# loud-esp-rev-f-schematic_easyeda.net
KiCad netlist of a schematic drawn in EasyEDA
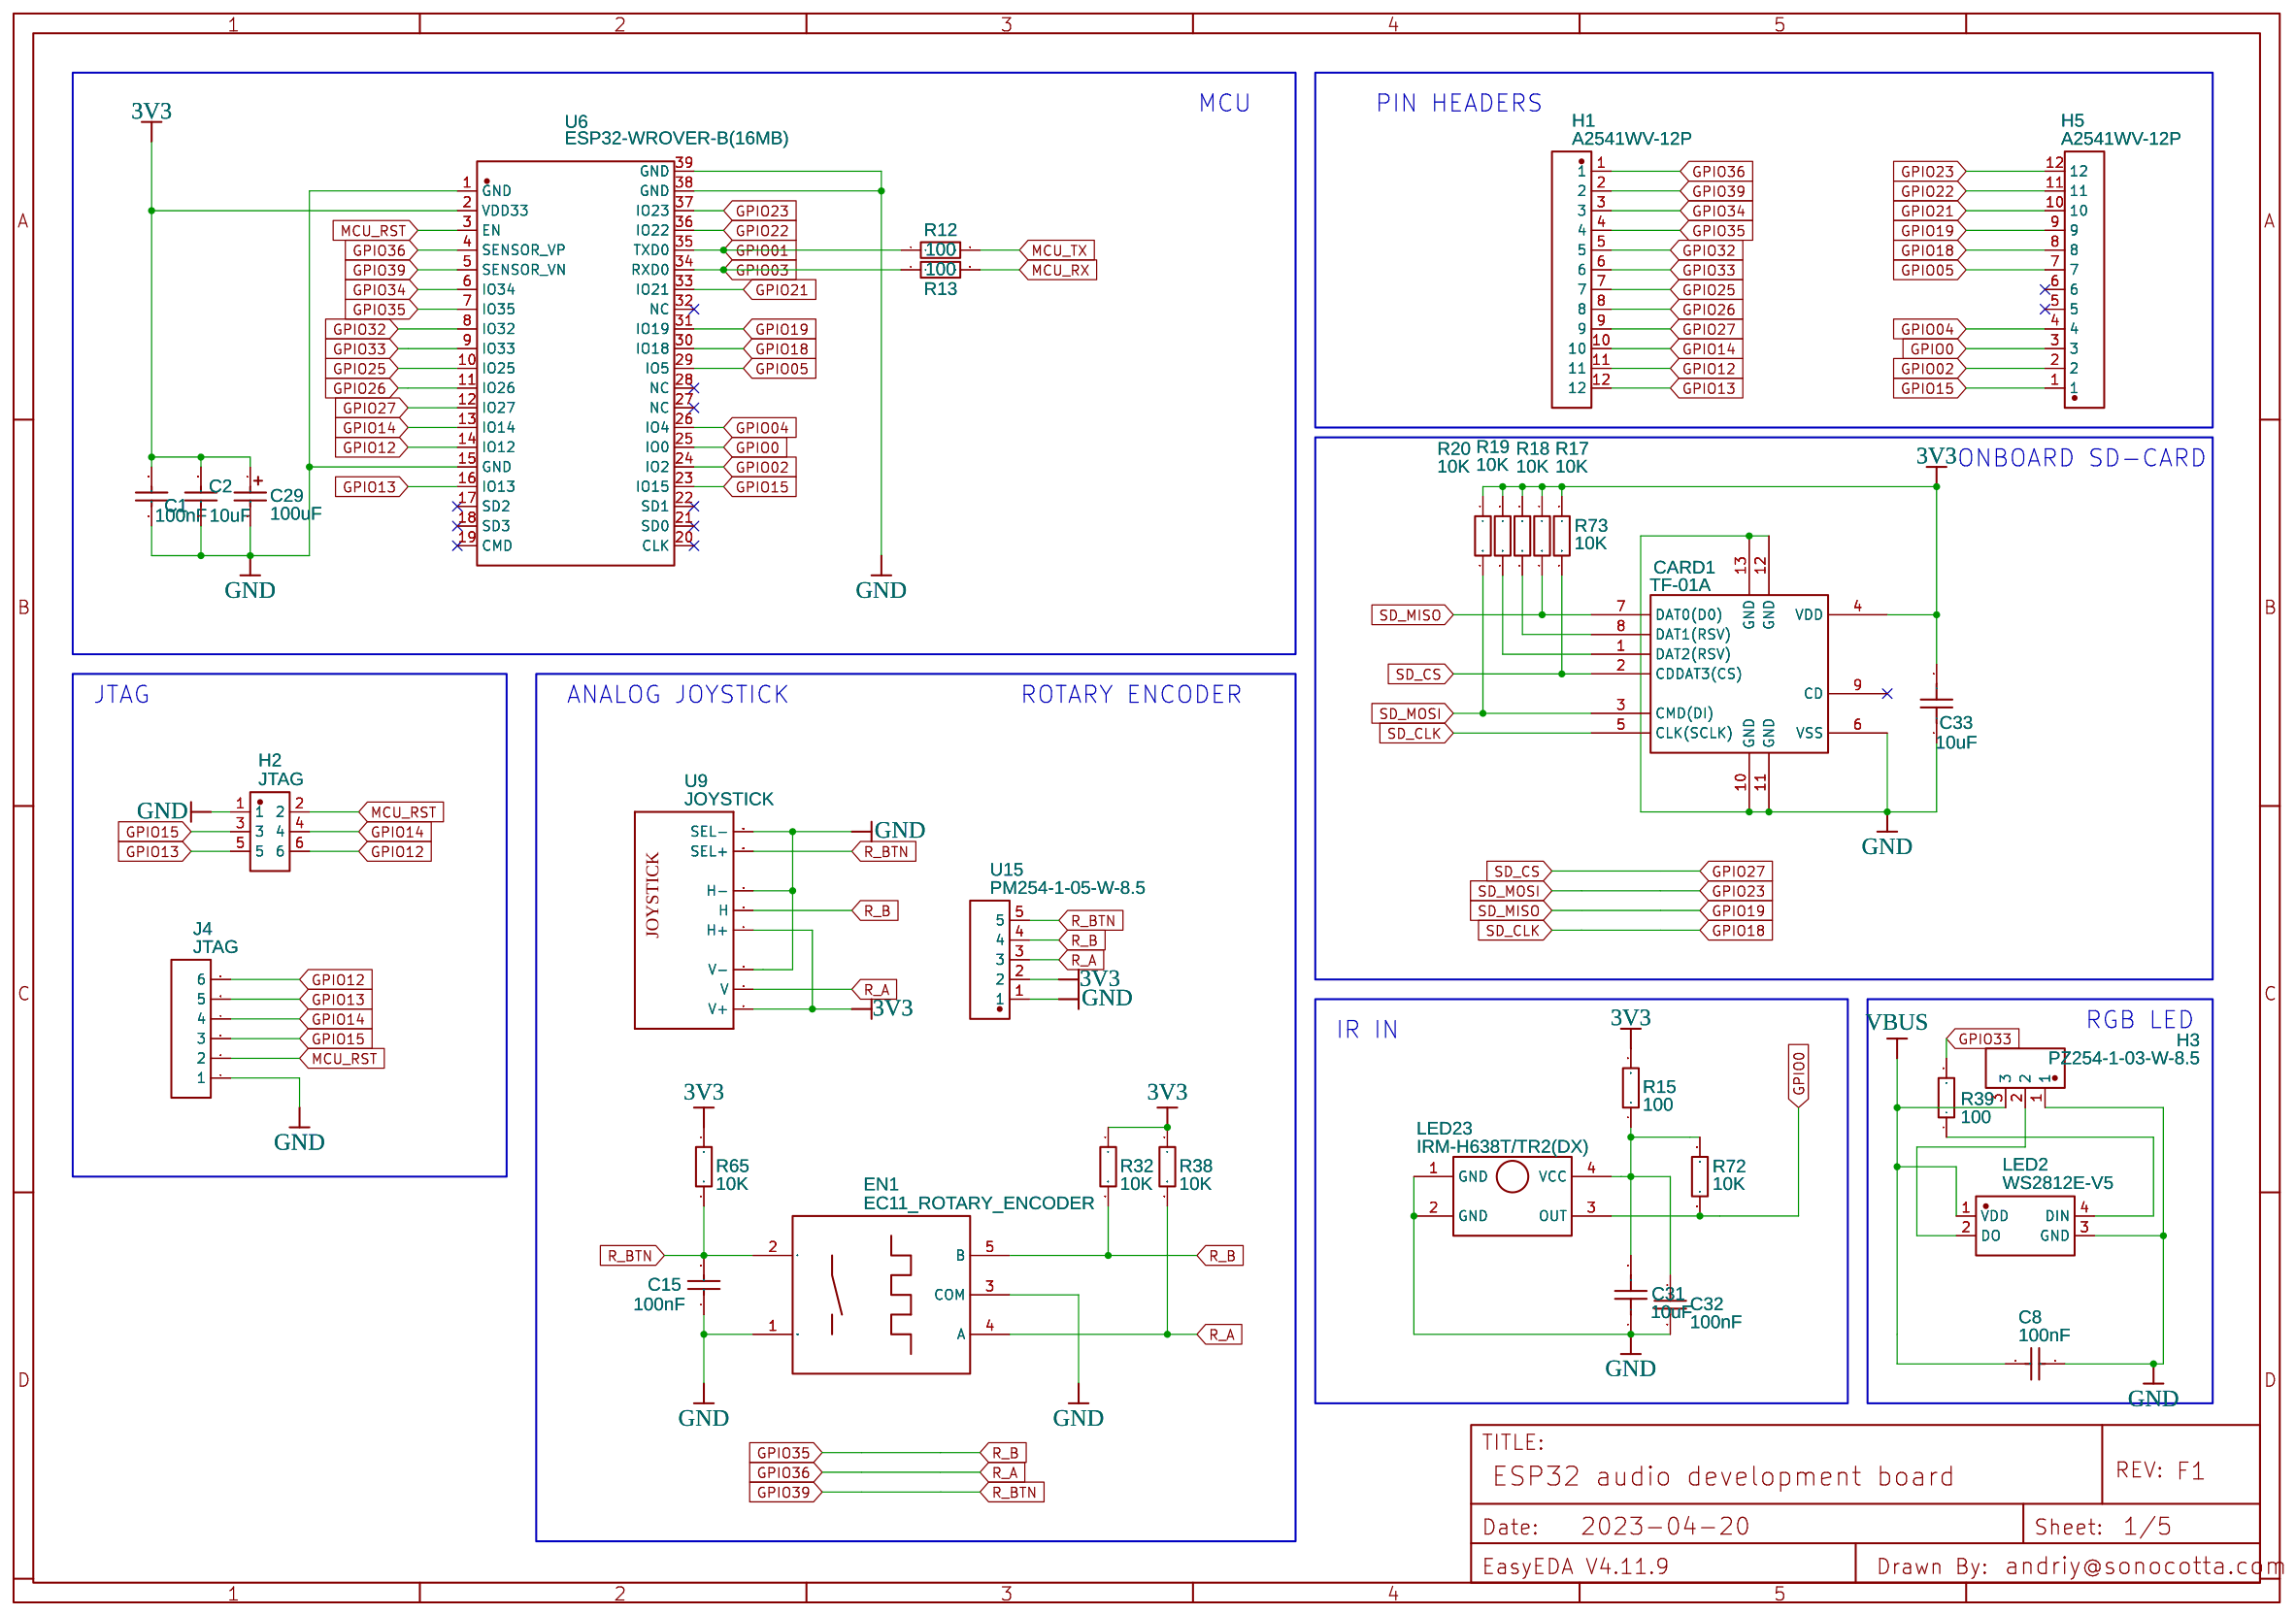
[diagram p0: MCU]
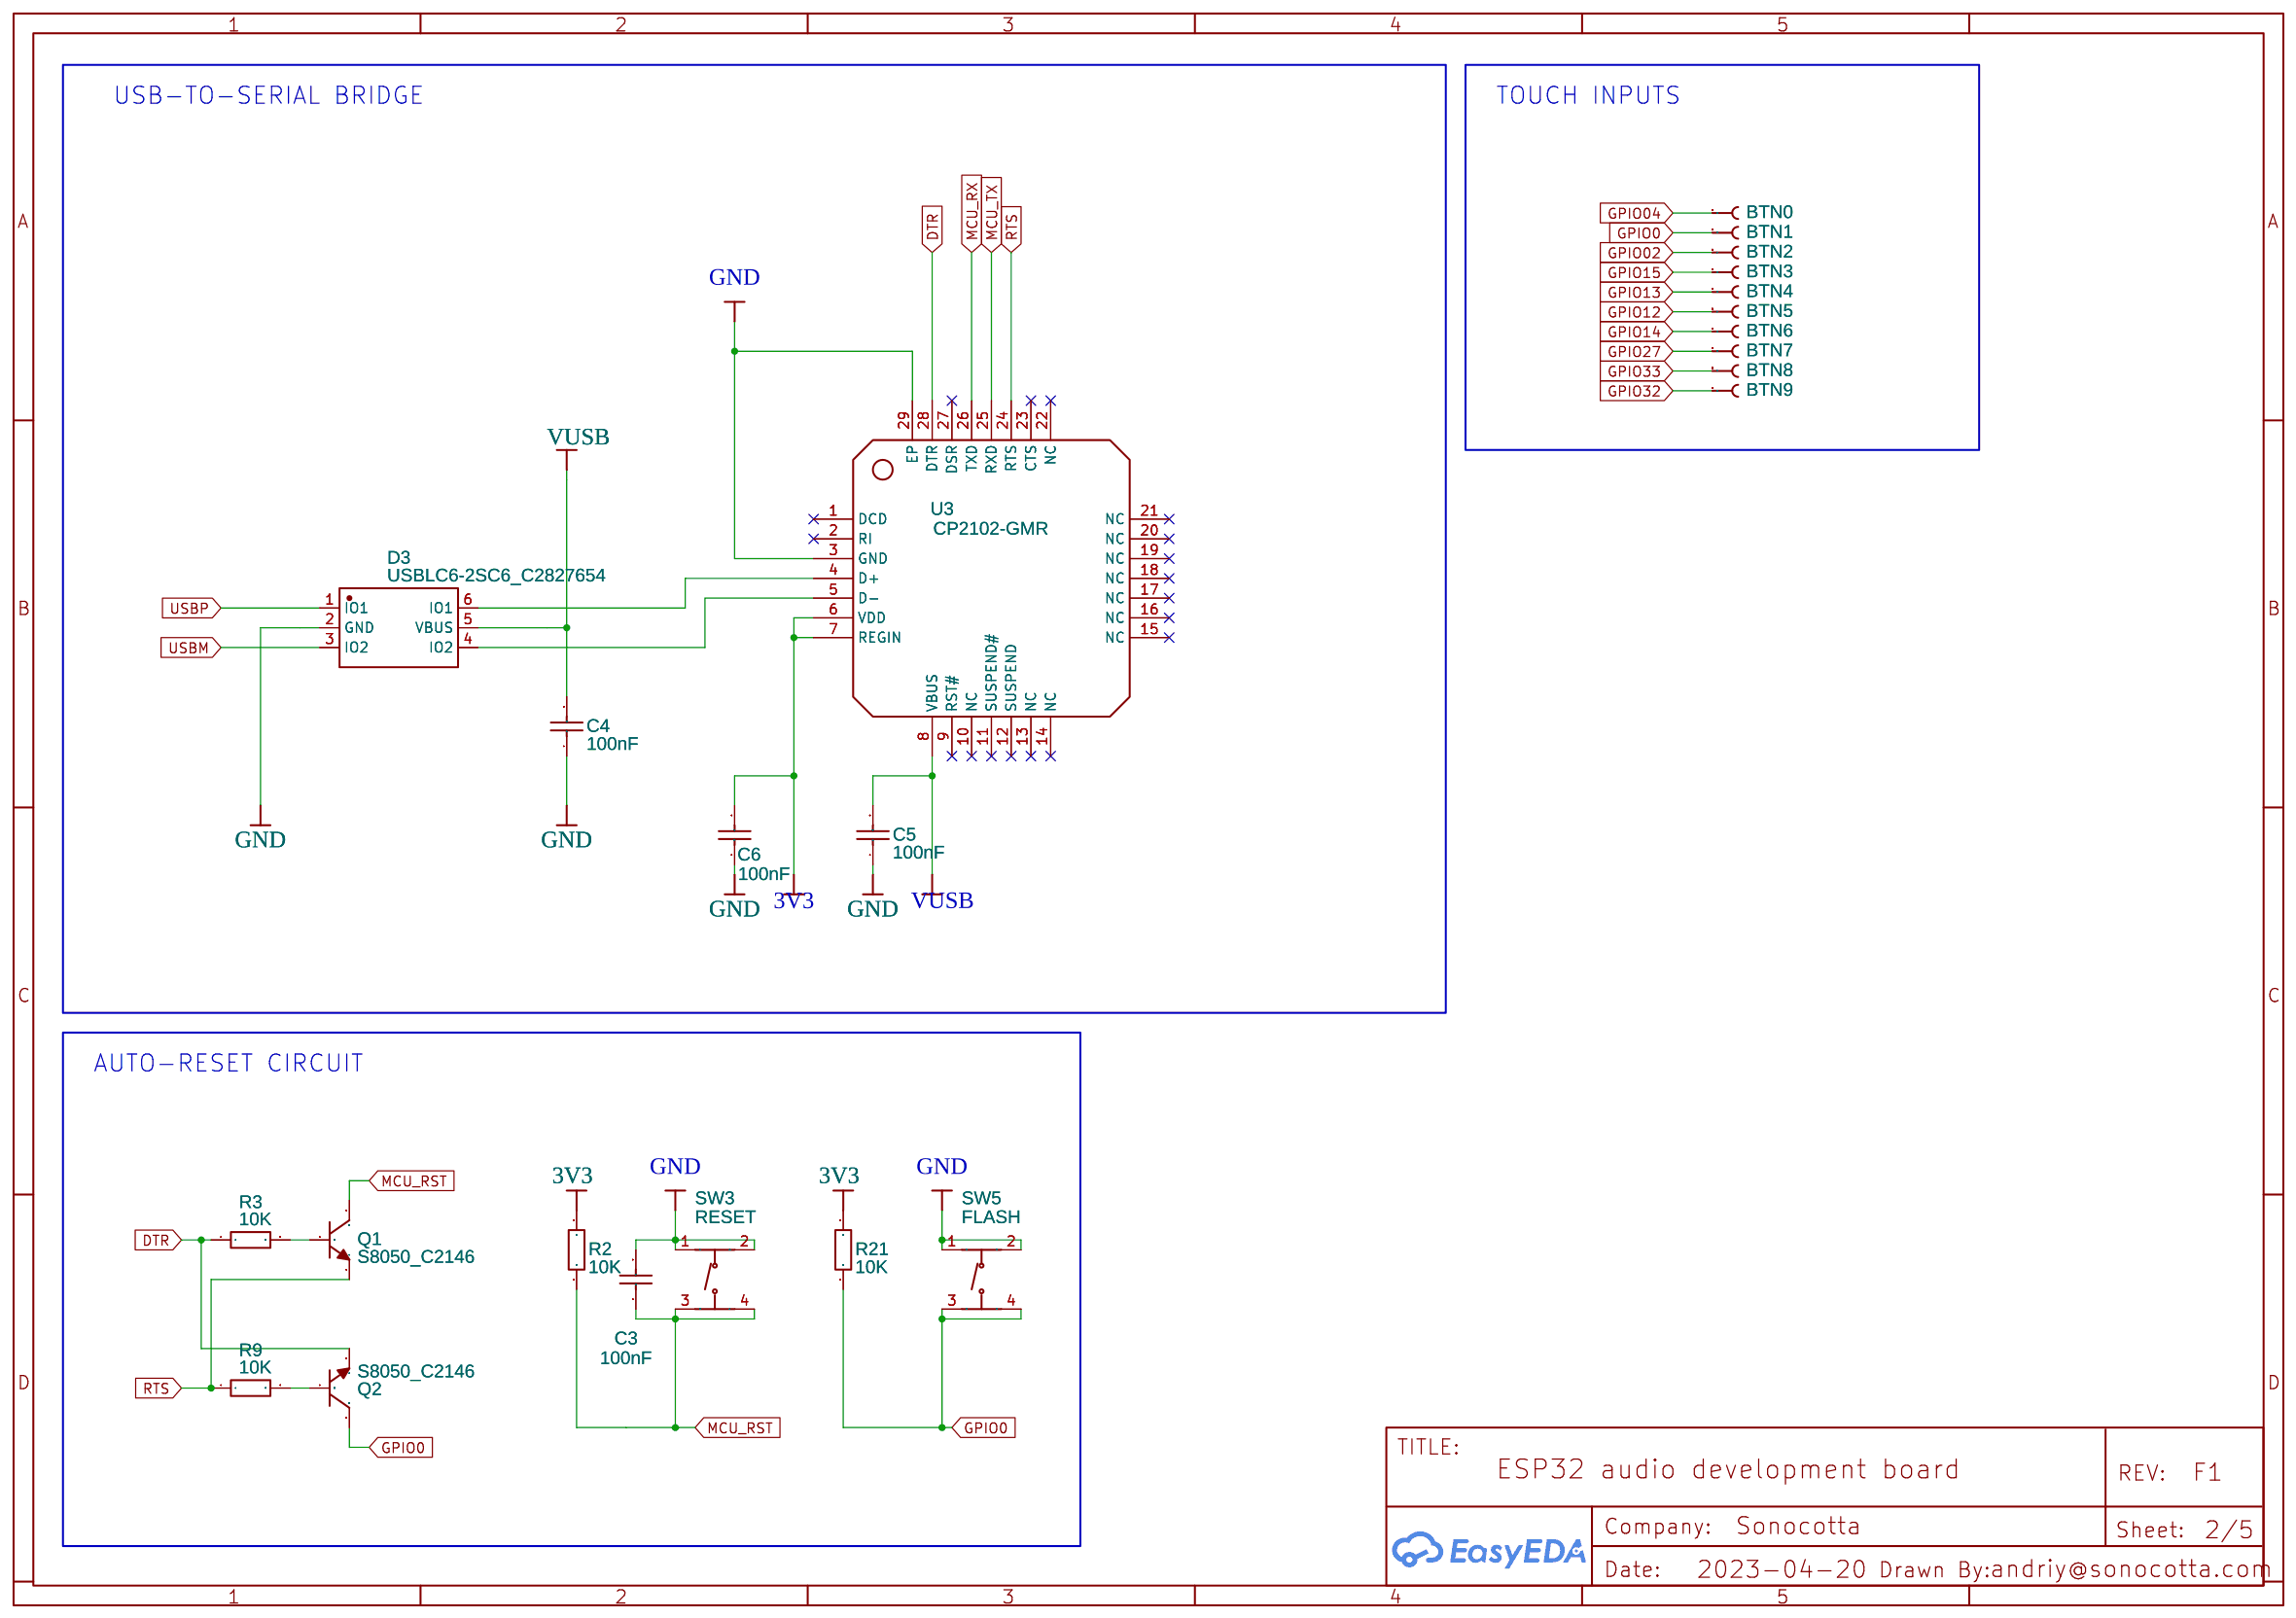
[diagram p1: SERIAL]
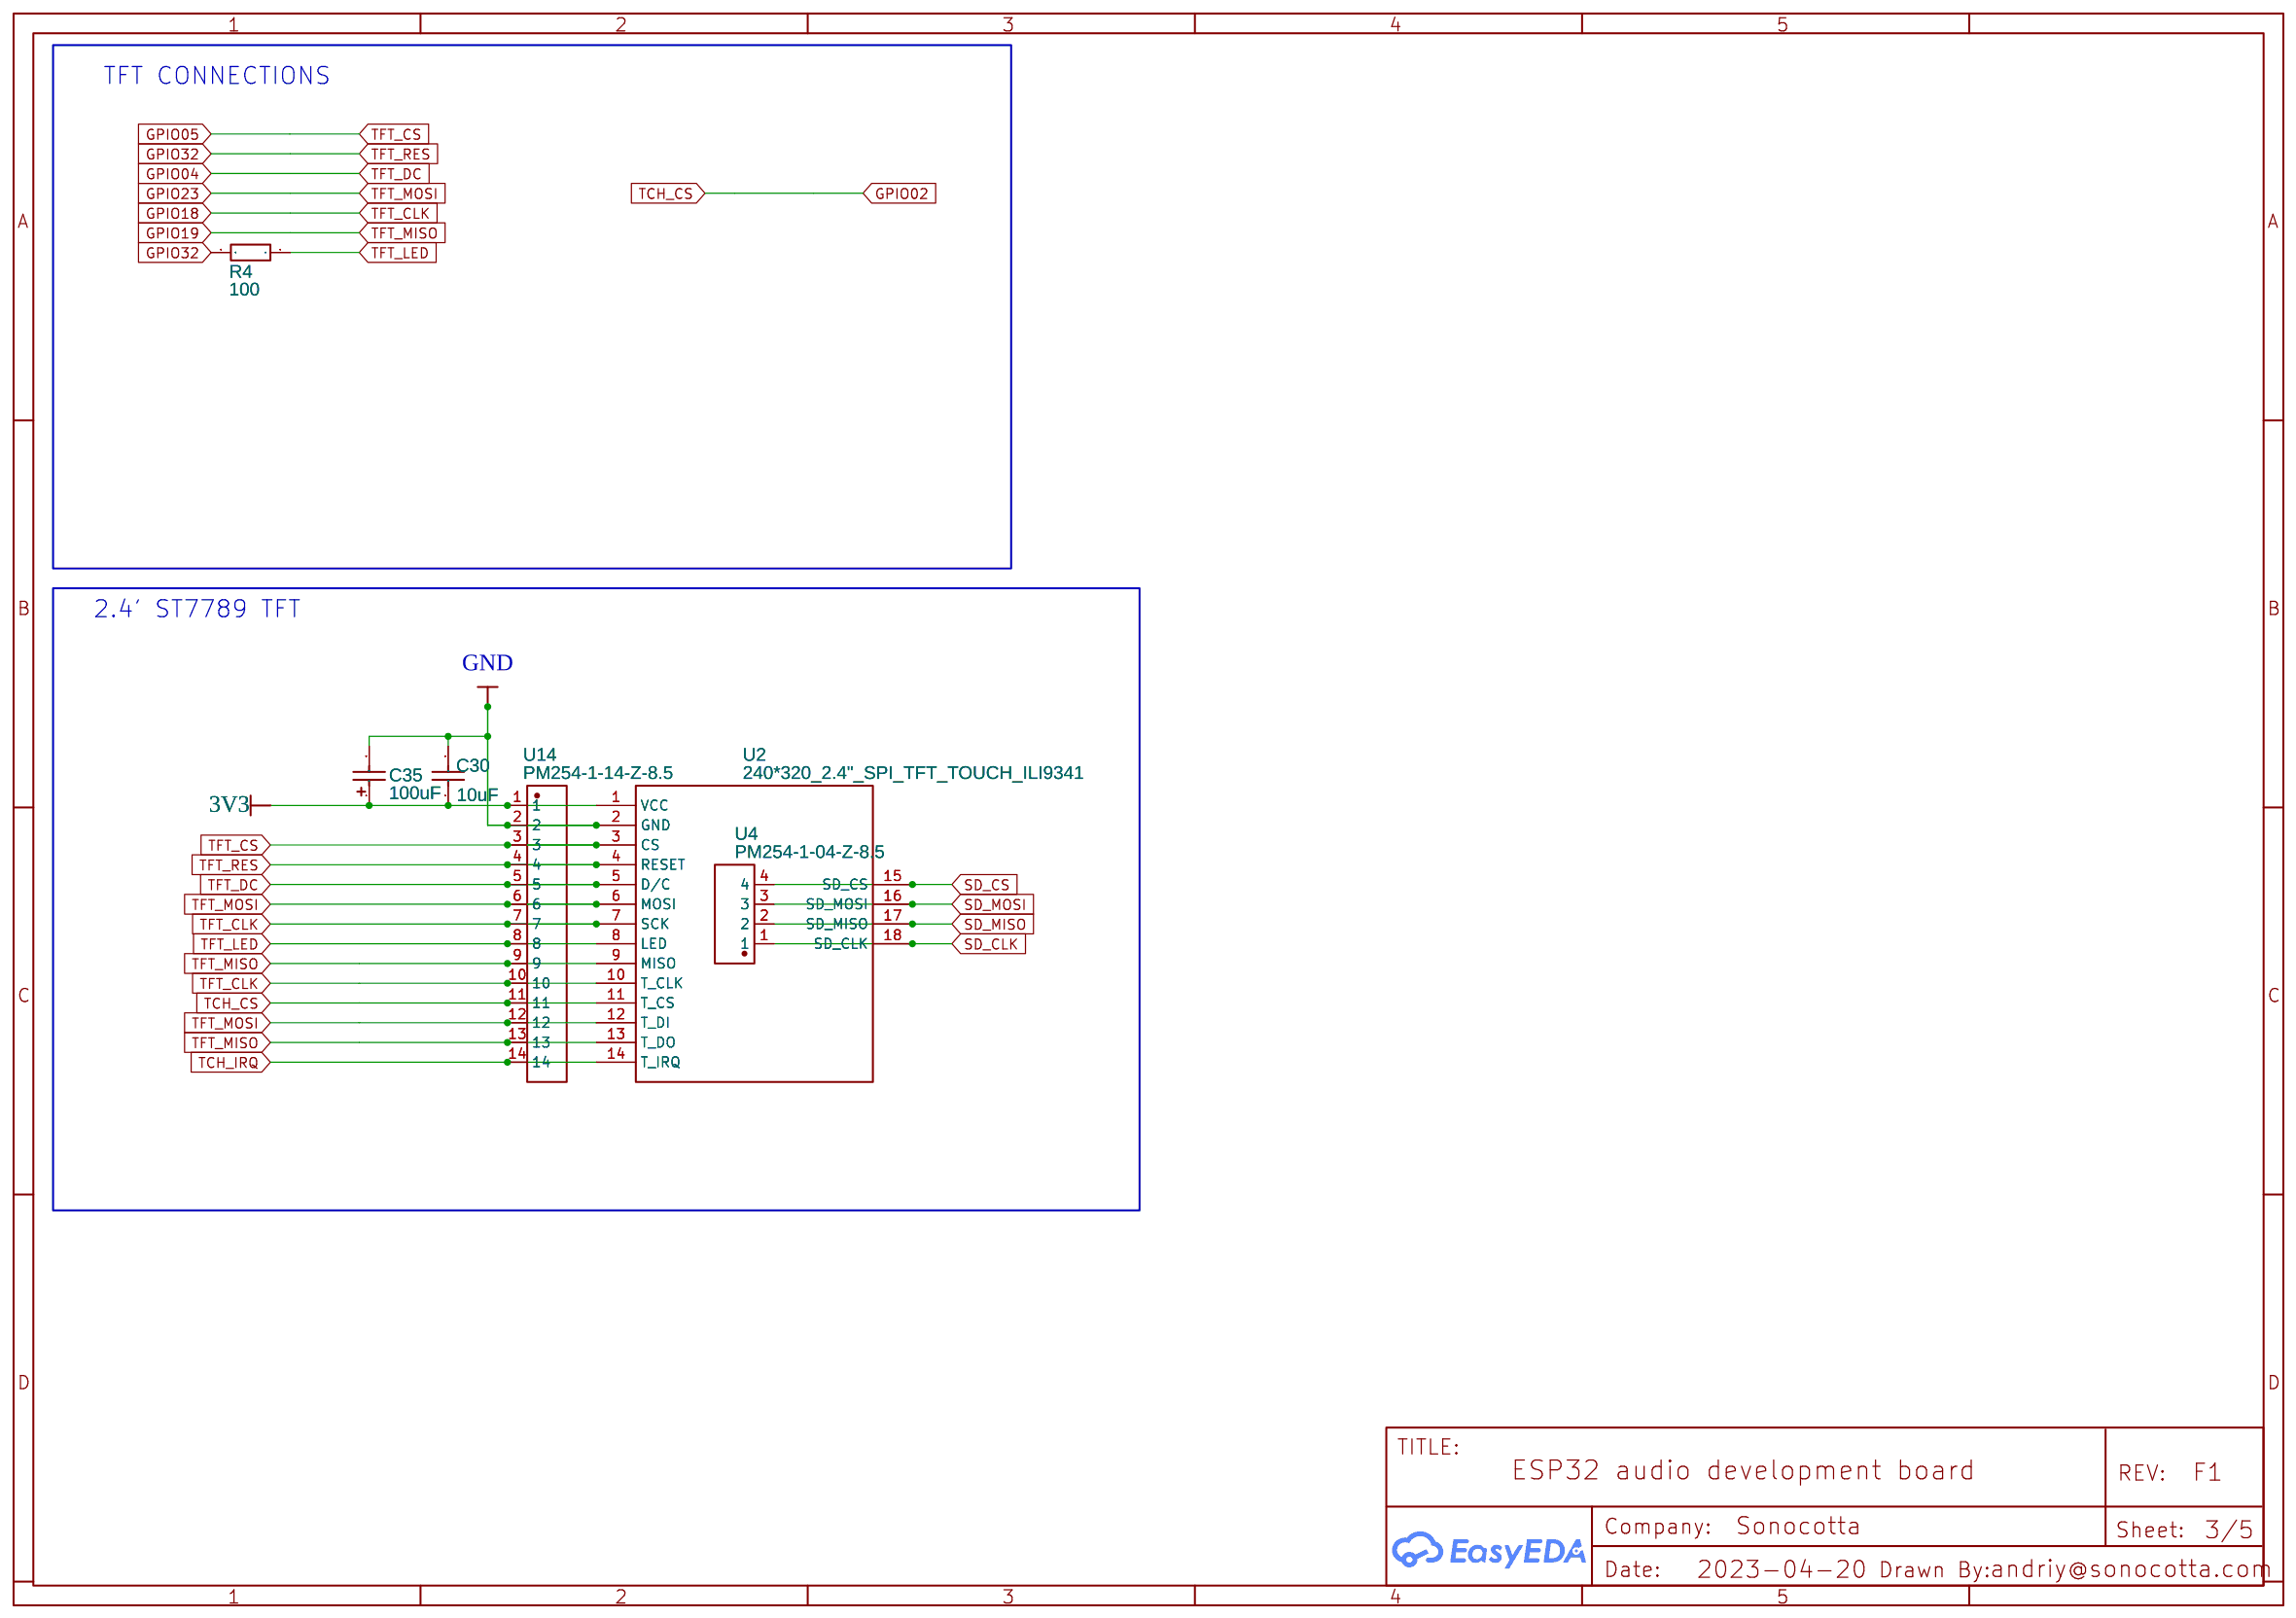
[diagram p2: VISUAL]
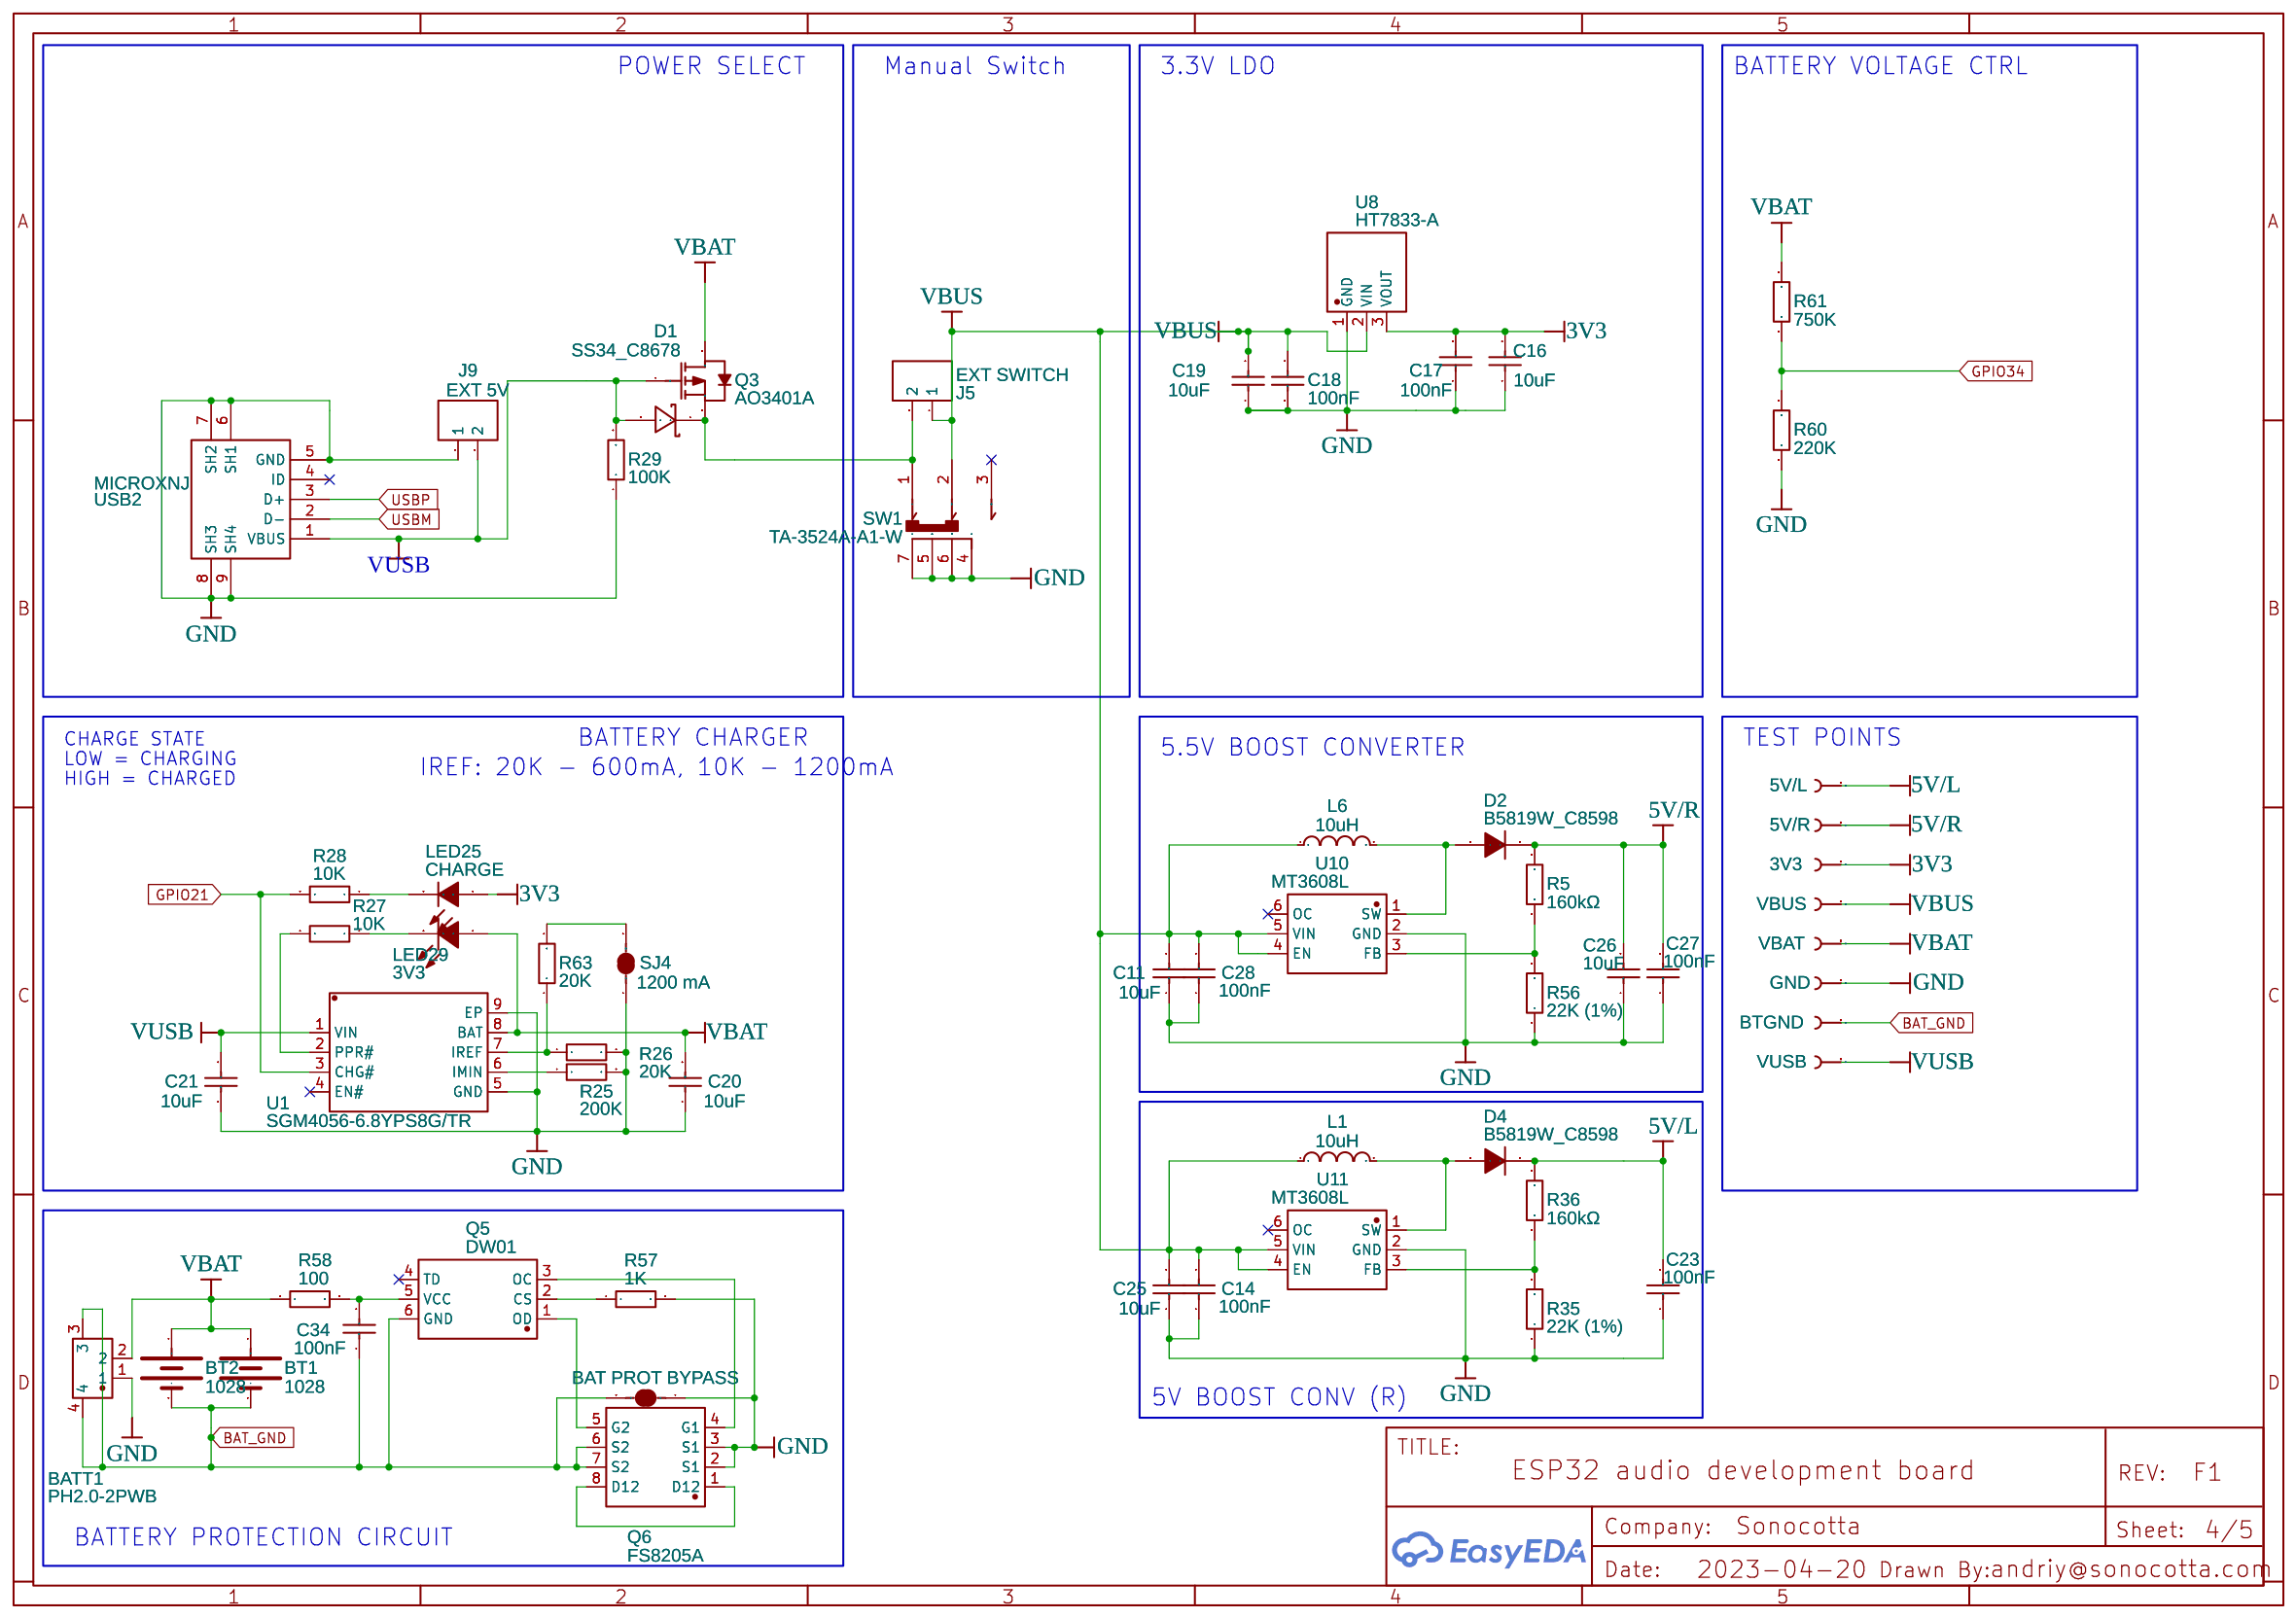
[diagram p3: POWER MGT]
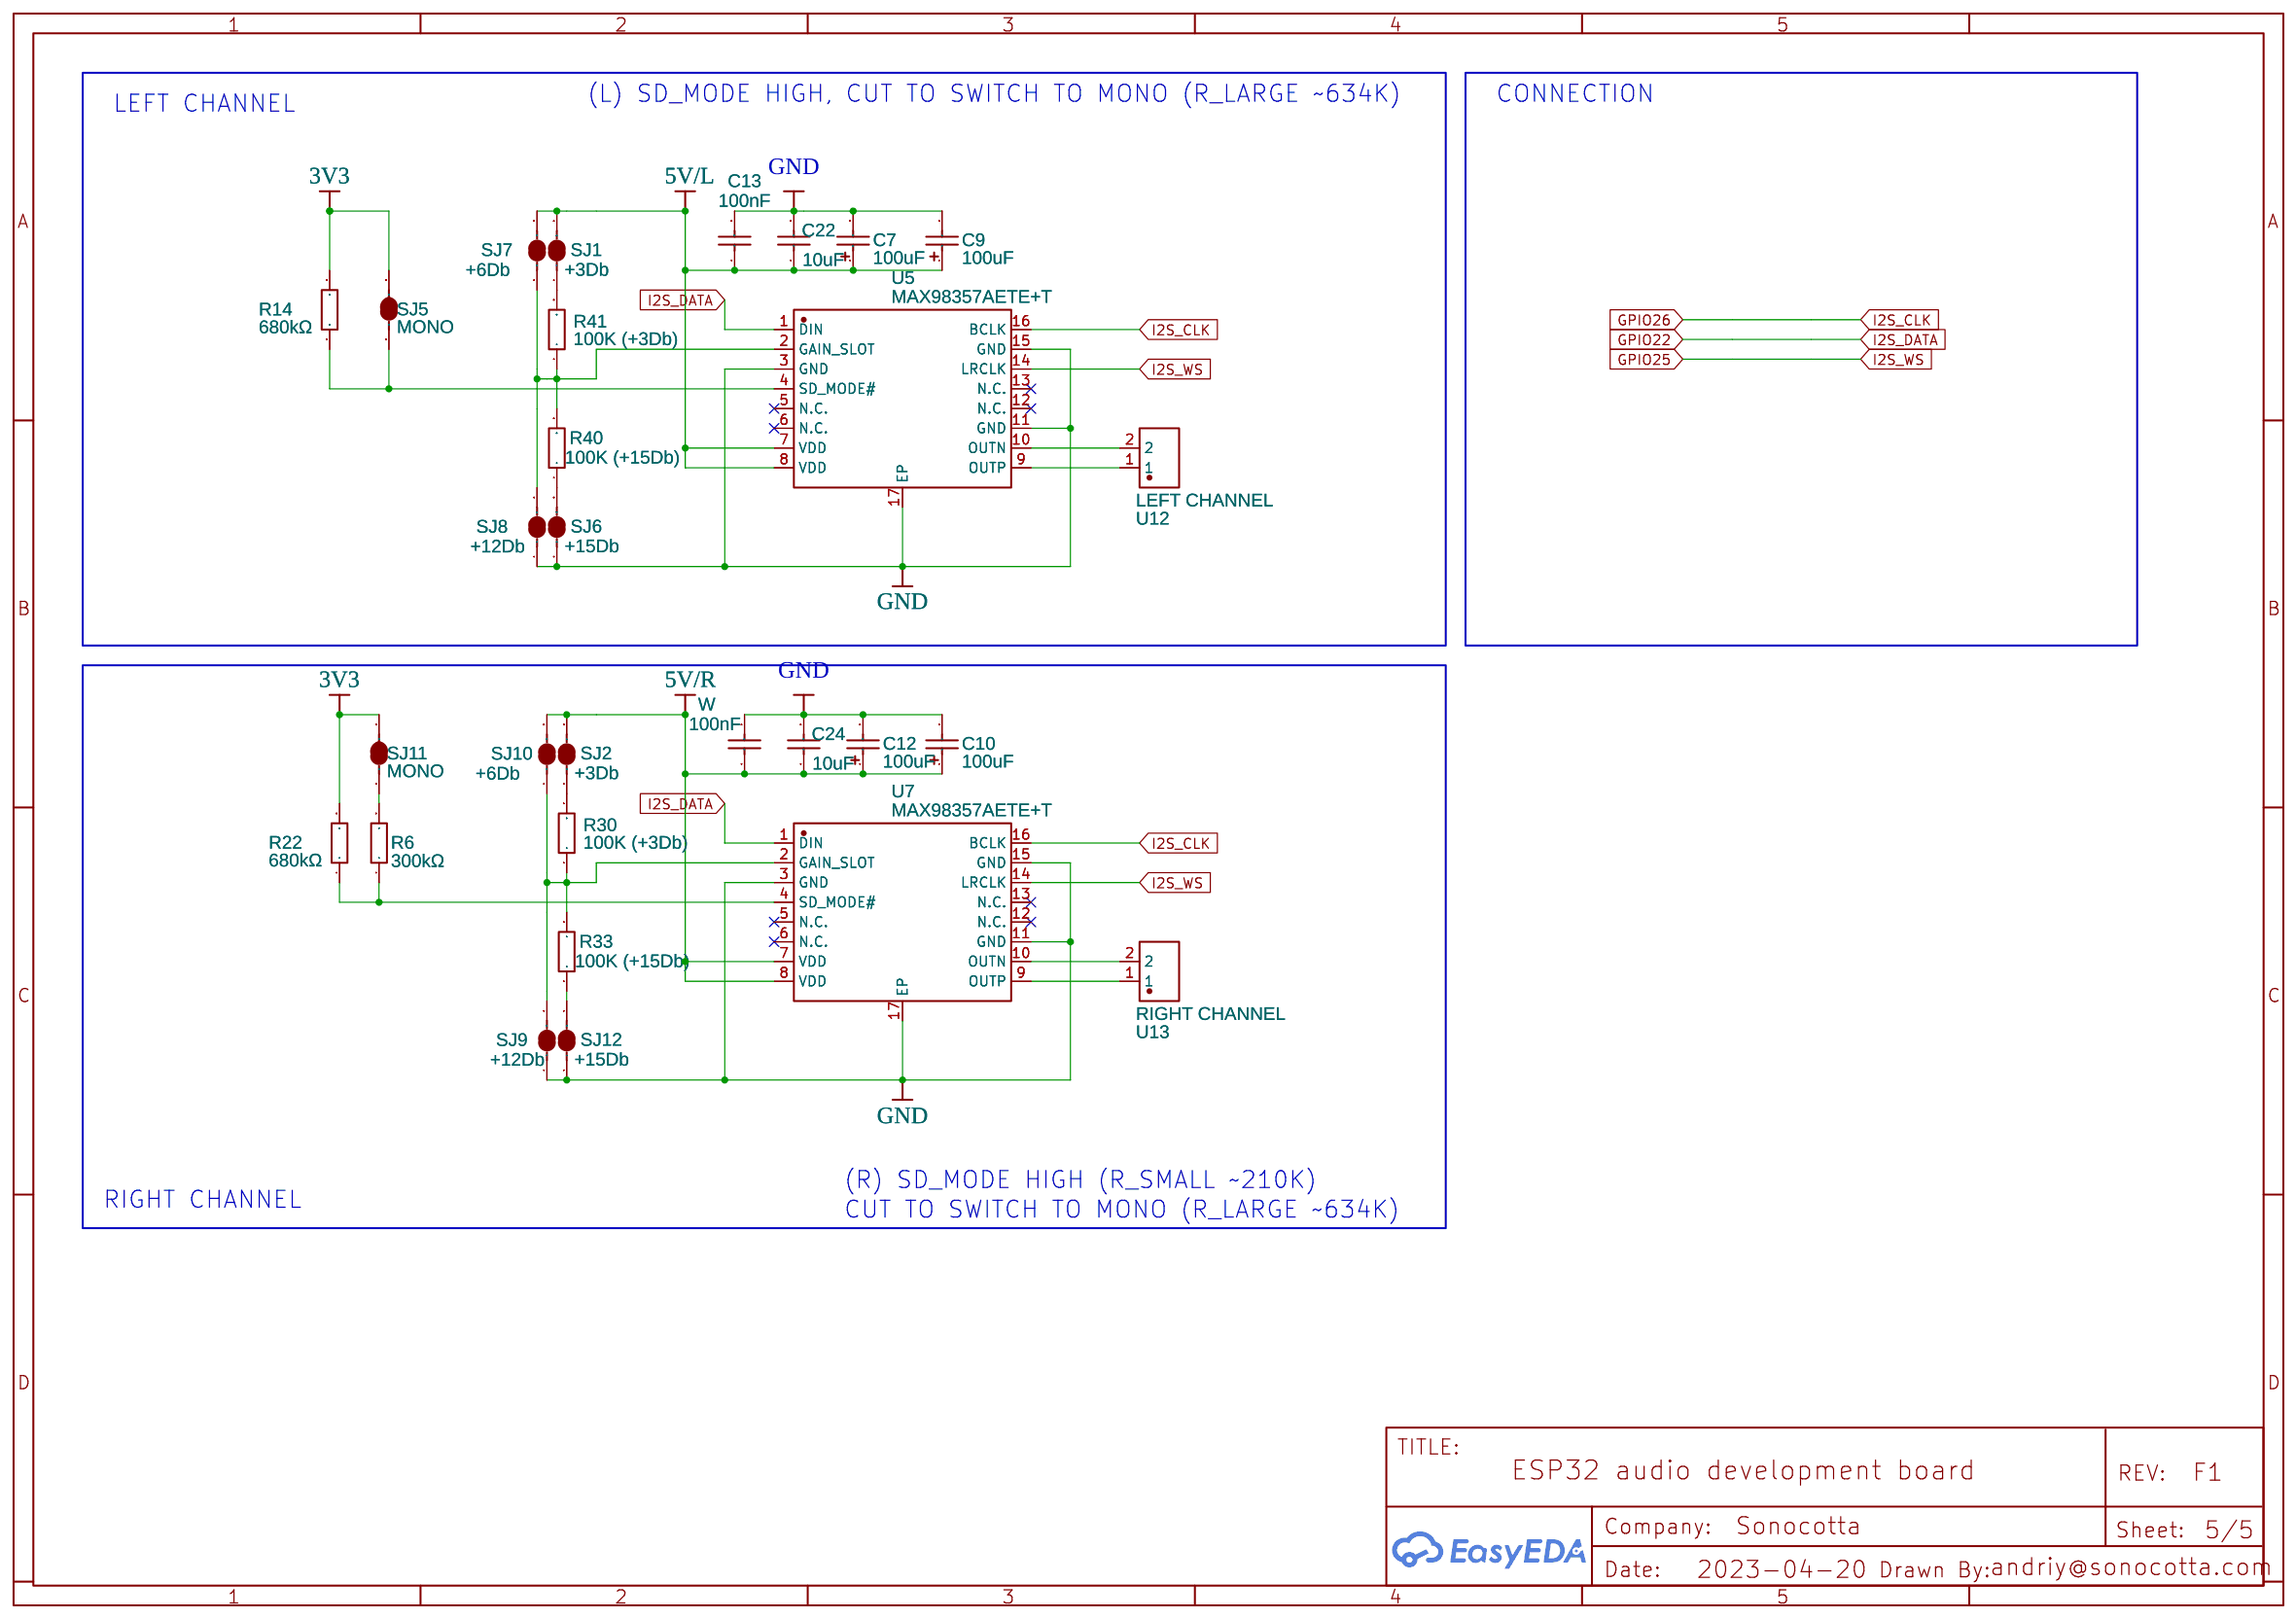
[diagram p4: DAC]

(export (version "E")
  (design (tool "Eeschema 10.0.6"))
  (components
    (comp (ref "C1")
      (value "100nF")
      (fields (field (name "Manufacturer Part") "CL05B104KO5NNNC") (field (name "Manufacturer") "SAMSUNG"))
      (libsource (lib "") (part "CL05B104KO5NNNC"))
    )
    (comp (ref "C2")
      (value "10uF")
      (fields (field (name "Manufacturer Part") "CL21A106KAYNNNE") (field (name "Manufacturer") "SAMSUNG"))
      (libsource (lib "") (part "CL21A106KAYNNNE"))
    )
    (comp (ref "C8")
      (value "100nF")
      (fields (field (name "Manufacturer Part") "CL05B104KO5NNNC") (field (name "Manufacturer") "SAMSUNG"))
      (libsource (lib "") (part "C0201X6S104K6R3NTA"))
    )
    (comp (ref "C15")
      (value "100nF")
      (fields (field (name "Manufacturer Part") "CL05B104KO5NNNC") (field (name "Manufacturer") "SAMSUNG"))
      (libsource (lib "") (part "CL05B104KO5NNNC"))
    )
    (comp (ref "C29")
      (value "100uF")
      (fields (field (name "Manufacturer Part") "TAJB107K006RNJ") (field (name "Manufacturer") "AVX"))
      (libsource (lib "") (part "TAJB107K006RNJ"))
    )
    (comp (ref "C31")
      (value "10uF")
      (fields (field (name "Manufacturer Part") "CL10A106KP8NNNC") (field (name "Manufacturer") "SAMSUNG"))
      (libsource (lib "") (part "JMK107ABJ106KA-T"))
    )
    (comp (ref "C32")
      (value "100nF")
      (fields (field (name "Manufacturer Part") "CL05B104KO5NNNC") (field (name "Manufacturer") "SAMSUNG"))
      (libsource (lib "") (part "CL05B104KO5NNNC_1"))
    )
    (comp (ref "C33")
      (value "10uF")
      (fields (field (name "Manufacturer Part") "CL10A106KP8NNNC") (field (name "Manufacturer") "SAMSUNG"))
      (libsource (lib "") (part "JMK107ABJ106KA-T"))
    )
    (comp (ref "CARD1")
      (value "TF-01A")
      (fields (field (name "Manufacturer") "HRO"))
      (libsource (lib "") (part "TF-01A"))
    )
    (comp (ref "EN1")
      (value "EC11_ROTARY_ENCODER")
      (fields (field (name "Manufacturer Part") "EC11 Rotary Encoder"))
      (libsource (lib "") (part "EC11_ROTARY_ENCODER"))
    )
    (comp (ref "H1")
      (value "A2541WV-12P")
      (fields (field (name "Manufacturer") "Changjiang Connectors"))
      (libsource (lib "") (part "A2541WV-12P_1"))
    )
    (comp (ref "H2")
      (value "JTAG")
      (fields
        (field (name "Manufacturer Part") "X4621WV-2×03I-C28D40")
        (field (name "Manufacturer") "XKB Connectivity")
      )
      (libsource (lib "") (part "X4621WV-2×03I-C28D40"))
    )
    (comp (ref "H3")
      (value "PZ254-1-03-W-8.5")
      (fields (field (name "Manufacturer") "HCTL(华灿天禄)"))
      (libsource (lib "") (part "PZ254-1-03-W-8.5"))
    )
    (comp (ref "H5")
      (value "A2541WV-12P")
      (fields (field (name "Manufacturer") "Changjiang Connectors"))
      (libsource (lib "") (part "A2541WV-12P"))
    )
    (comp (ref "J4") (value "JTAG") (libsource (lib "") (part "HDR-M-2.54_1x6")))
    (comp (ref "LED2")
      (value "WS2812E-V5")
      (fields (field (name "Manufacturer") "worldsemi"))
      (libsource (lib "") (part "WS2812E-V5"))
    )
    (comp (ref "LED23")
      (value "IRM-H638T/TR2(DX)")
      (fields (field (name "Manufacturer") "Everlight Elec"))
      (libsource (lib "") (part "IRM-H638T/TR2(DX)"))
    )
    (comp (ref "R12")
      (value "100")
      (fields (field (name "Manufacturer Part") "0402WGF1000TCE") (field (name "Manufacturer") "UniOhm"))
      (libsource (lib "") (part "0402WGF1000TCE_1"))
    )
    (comp (ref "R13")
      (value "100")
      (fields (field (name "Manufacturer Part") "0402WGF1000TCE") (field (name "Manufacturer") "UniOhm"))
      (libsource (lib "") (part "0402WGF1000TCE_1"))
    )
    (comp (ref "R15")
      (value "100")
      (fields (field (name "Manufacturer Part") "0402WGF1000TCE") (field (name "Manufacturer") "UniOhm"))
      (libsource (lib "") (part "0402WGF1000TCE"))
    )
    (comp (ref "R17")
      (value "10K")
      (fields (field (name "Manufacturer Part") "0402WGF1002TCE") (field (name "Manufacturer") "UniOhm"))
      (libsource (lib "") (part "0402WGF1002TCE"))
    )
    (comp (ref "R18")
      (value "10K")
      (fields (field (name "Manufacturer Part") "0402WGF1002TCE") (field (name "Manufacturer") "UniOhm"))
      (libsource (lib "") (part "0402WGF1002TCE"))
    )
    (comp (ref "R19")
      (value "10K")
      (fields (field (name "Manufacturer Part") "0402WGF1002TCE") (field (name "Manufacturer") "UniOhm"))
      (libsource (lib "") (part "0402WGF1002TCE"))
    )
    (comp (ref "R20")
      (value "10K")
      (fields (field (name "Manufacturer Part") "0402WGF1002TCE") (field (name "Manufacturer") "UniOhm"))
      (libsource (lib "") (part "0402WGF1002TCE"))
    )
    (comp (ref "R32")
      (value "10K")
      (fields (field (name "Manufacturer Part") "0402WGF1002TCE") (field (name "Manufacturer") "UniOhm"))
      (libsource (lib "") (part "0402WGF1002TCE"))
    )
    (comp (ref "R38")
      (value "10K")
      (fields (field (name "Manufacturer Part") "0402WGF1002TCE") (field (name "Manufacturer") "UniOhm"))
      (libsource (lib "") (part "0402WGF1002TCE"))
    )
    (comp (ref "R39")
      (value "100")
      (fields (field (name "Manufacturer Part") "0402WGF1000TCE") (field (name "Manufacturer") "UniOhm"))
      (libsource (lib "") (part "0402WGF1000TCE"))
    )
    (comp (ref "R65")
      (value "10K")
      (fields (field (name "Manufacturer Part") "0402WGF1002TCE") (field (name "Manufacturer") "UniOhm"))
      (libsource (lib "") (part "0402WGF1002TCE"))
    )
    (comp (ref "R72")
      (value "10K")
      (fields (field (name "Manufacturer Part") "0402WGF1002TCE") (field (name "Manufacturer") "UniOhm"))
      (libsource (lib "") (part "0402WGF1002TCE"))
    )
    (comp (ref "R73")
      (value "10K")
      (fields (field (name "Manufacturer Part") "0402WGF1002TCE") (field (name "Manufacturer") "UniOhm"))
      (libsource (lib "") (part "0402WGF1002TCE"))
    )
    (comp (ref "U6")
      (value "ESP32-WROVER-B(16MB)")
      (fields (field (name "Manufacturer") "Espressif Systems"))
      (libsource (lib "") (part "ESP32-WROVER-B(16MB)"))
    )
    (comp (ref "U9") (value "JOYSTICK") (libsource (lib "") (part "JOYSTICK")))
    (comp (ref "U15")
      (value "PM254-1-05-W-8.5")
      (fields (field (name "Manufacturer") "HCTL(华灿天禄)"))
      (libsource (lib "") (part "PM254-1-05-W-8.5"))
    )
    (comp (ref "BTN0") (value "SENSOR CAP 1") (libsource (lib "") (part "TEST-POINT2")))
    (comp (ref "BTN1") (value "SENSOR CAP 1") (libsource (lib "") (part "TEST-POINT2")))
    (comp (ref "BTN2") (value "SENSOR CAP 1") (libsource (lib "") (part "TEST-POINT2")))
    (comp (ref "BTN3") (value "SENSOR CAP 1") (libsource (lib "") (part "TEST-POINT2")))
    (comp (ref "BTN4") (value "SENSOR CAP 1") (libsource (lib "") (part "TEST-POINT2")))
    (comp (ref "BTN5") (value "SENSOR CAP 1") (libsource (lib "") (part "TEST-POINT2")))
    (comp (ref "BTN6") (value "SENSOR CAP 1") (libsource (lib "") (part "TEST-POINT2")))
    (comp (ref "BTN7") (value "SENSOR CAP 1") (libsource (lib "") (part "TEST-POINT2")))
    (comp (ref "BTN8") (value "SENSOR CAP 1") (libsource (lib "") (part "TEST-POINT2")))
    (comp (ref "BTN9") (value "SENSOR CAP 1") (libsource (lib "") (part "TEST-POINT2")))
    (comp (ref "C3")
      (value "100nF")
      (fields
        (field (name "BOM_Manufacturer Part") "CL05B104KO5NNNC")
        (field (name "BOM_Supplier Part") "C1525")
      )
      (libsource (lib "") (part "CL05B104KO5NNNC"))
    )
    (comp (ref "C4")
      (value "100nF")
      (fields
        (field (name "BOM_Manufacturer Part") "CL05B104KO5NNNC")
        (field (name "BOM_Supplier Part") "C1525")
      )
      (libsource (lib "") (part "CL05B104KO5NNNC"))
    )
    (comp (ref "C5")
      (value "100nF")
      (fields
        (field (name "BOM_Manufacturer Part") "CL05B104KO5NNNC")
        (field (name "BOM_Supplier Part") "C1525")
      )
      (libsource (lib "") (part "CL05B104KO5NNNC"))
    )
    (comp (ref "C6")
      (value "100nF")
      (fields
        (field (name "BOM_Manufacturer Part") "CL05B104KO5NNNC")
        (field (name "BOM_Supplier Part") "C1525")
      )
      (libsource (lib "") (part "CL05B104KO5NNNC"))
    )
    (comp (ref "D3")
      (value "USBLC6-2SC6_C2827654")
      (fields
        (field (name "BOM_Manufacturer Part") "USBLC6-2SC6")
        (field (name "BOM_Supplier Part") "C2827654")
      )
      (libsource (lib "") (part "USBLC6-2SC6_C2827654"))
    )
    (comp (ref "Q1")
      (value "S8050_C2146")
      (fields (field (name "BOM_Manufacturer Part") "S8050") (field (name "BOM_Supplier Part") "C2146"))
      (libsource (lib "") (part "S8050_C2146"))
    )
    (comp (ref "Q2")
      (value "S8050_C2146")
      (fields (field (name "BOM_Manufacturer Part") "S8050") (field (name "BOM_Supplier Part") "C2146"))
      (libsource (lib "") (part "S8050_C2146_1"))
    )
    (comp (ref "R2")
      (value "10K")
      (fields
        (field (name "BOM_Manufacturer Part") "0402WGF1002TCE")
        (field (name "BOM_Supplier Part") "C25744")
      )
      (libsource (lib "") (part "0402WGF1002TCE_1"))
    )
    (comp (ref "R3")
      (value "10K")
      (fields
        (field (name "BOM_Manufacturer Part") "0402WGF1002TCE")
        (field (name "BOM_Supplier Part") "C25744")
      )
      (libsource (lib "") (part "0402WGF1002TCE"))
    )
    (comp (ref "R9")
      (value "10K")
      (fields
        (field (name "BOM_Manufacturer Part") "0402WGF1002TCE")
        (field (name "BOM_Supplier Part") "C25744")
      )
      (libsource (lib "") (part "0402WGF1002TCE"))
    )
    (comp (ref "R21")
      (value "10K")
      (fields
        (field (name "BOM_Manufacturer Part") "0402WGF1002TCE")
        (field (name "BOM_Supplier Part") "C25744")
      )
      (libsource (lib "") (part "0402WGF1002TCE_1"))
    )
    (comp (ref "SW3")
      (value "RESET")
      (fields
        (field (name "BOM_Manufacturer Part") "TS-1187A-B-A-B")
        (field (name "BOM_Supplier Part") "C318884")
      )
      (libsource (lib "") (part "TS-1187A-B-A-B"))
    )
    (comp (ref "SW5")
      (value "FLASH")
      (fields
        (field (name "BOM_Manufacturer Part") "TS-1187A-B-A-B")
        (field (name "BOM_Supplier Part") "C318884")
      )
      (libsource (lib "") (part "TS-1187A-B-A-B"))
    )
    (comp (ref "U3")
      (value "CP2102-GMR")
      (fields (field (name "BOM_Supplier Part") "C6568"))
      (libsource (lib "") (part "CP2102-GMR"))
    )
    (comp (ref "C30")
      (value "10uF")
      (fields
        (field (name "BOM_Manufacturer Part") "CL21A106KAYNNNE")
        (field (name "BOM_Supplier Part") "C15850")
      )
      (libsource (lib "") (part "CL21A106KAYNNNE"))
    )
    (comp (ref "C35")
      (value "100uF")
      (fields
        (field (name "BOM_Manufacturer Part") "TAJB107K006RNJ")
        (field (name "BOM_Supplier Part") "C16133")
      )
      (libsource (lib "") (part "TAJB107K006RNJ"))
    )
    (comp (ref "R4")
      (value "100")
      (fields
        (field (name "BOM_Manufacturer Part") "0402WGF1000TCE")
        (field (name "BOM_Supplier Part") "C25076")
      )
      (libsource (lib "") (part "0402WGF1000TCE"))
    )
    (comp (ref "U2")
      (value "240*320_2.4\"_SPI_TFT_TOUCH_ILI9341")
      (libsource (lib "") (part "240*320_2.4{dblquote}_SPI_TFT_TOUCH_ILI9341"))
    )
    (comp (ref "U4")
      (value "PM254-1-04-Z-8.5")
      (fields (field (name "BOM_Supplier Part") "C2897367"))
      (libsource (lib "") (part "PM254-1-04-Z-8.5"))
    )
    (comp (ref "U14")
      (value "PM254-1-14-Z-8.5")
      (fields (field (name "BOM_Supplier Part") "C2897377"))
      (libsource (lib "") (part "PM254-1-14-Z-8.5"))
    )
    (comp (ref "3V3") (value "SENSOR CAP 1") (libsource (lib "") (part "TEST-POINT2_2")))
    (comp (ref "5V/L") (value "SENSOR CAP 1") (libsource (lib "") (part "TEST-POINT2_1")))
    (comp (ref "5V/R") (value "SENSOR CAP 1") (libsource (lib "") (part "TEST-POINT2_3")))
    (comp (ref "BATT1")
      (value "PH2.0-2PWB")
      (fields
        (field (name "BOM_Manufacturer Part") "PH2.0-2PWB Horizontal")
        (field (name "BOM_Supplier Part") "C47647")
      )
      (libsource (lib "") (part "PH2.0-2PWB"))
    )
    (comp (ref "BT1")
      (value "1028")
      (fields (field (name "BOM_Supplier Part") "C238063"))
      (libsource (lib "") (part "1028"))
    )
    (comp (ref "BT2")
      (value "1028")
      (fields (field (name "BOM_Supplier Part") "C238063"))
      (libsource (lib "") (part "1028"))
    )
    (comp (ref "BTGND") (value "SENSOR CAP 1") (libsource (lib "") (part "TEST-POINT2_7")))
    (comp (ref "C11")
      (value "10uF")
      (fields
        (field (name "BOM_Manufacturer Part") "CL21A106KAYNNNE")
        (field (name "BOM_Supplier Part") "C15850")
      )
      (libsource (lib "") (part "CL21A106KAYNNNE"))
    )
    (comp (ref "C14")
      (value "100nF")
      (fields
        (field (name "BOM_Manufacturer Part") "CL05B104KO5NNNC")
        (field (name "BOM_Supplier Part") "C1525")
      )
      (libsource (lib "") (part "CL05B104KO5NNNC"))
    )
    (comp (ref "C16")
      (value "10uF")
      (fields
        (field (name "BOM_Manufacturer Part") "CL21A106KAYNNNE")
        (field (name "BOM_Supplier Part") "C15850")
      )
      (libsource (lib "") (part "CL21A106KAYNNNE"))
    )
    (comp (ref "C17")
      (value "100nF")
      (fields
        (field (name "BOM_Manufacturer Part") "CL05B104KO5NNNC")
        (field (name "BOM_Supplier Part") "C1525")
      )
      (libsource (lib "") (part "CL05B104KO5NNNC"))
    )
    (comp (ref "C18")
      (value "100nF")
      (fields
        (field (name "BOM_Manufacturer Part") "CL05B104KO5NNNC")
        (field (name "BOM_Supplier Part") "C1525")
      )
      (libsource (lib "") (part "CL05B104KO5NNNC"))
    )
    (comp (ref "C19")
      (value "10uF")
      (fields
        (field (name "BOM_Manufacturer Part") "CL21A106KAYNNNE")
        (field (name "BOM_Supplier Part") "C15850")
      )
      (libsource (lib "") (part "CL21A106KAYNNNE"))
    )
    (comp (ref "C20")
      (value "10uF")
      (fields
        (field (name "BOM_Manufacturer Part") "CL21A106KAYNNNE")
        (field (name "BOM_Supplier Part") "C15850")
      )
      (libsource (lib "") (part "CL21A106KAYNNNE"))
    )
    (comp (ref "C21")
      (value "10uF")
      (fields
        (field (name "BOM_Manufacturer Part") "CL21A106KAYNNNE")
        (field (name "BOM_Supplier Part") "C15850")
      )
      (libsource (lib "") (part "CL21A106KAYNNNE"))
    )
    (comp (ref "C23")
      (value "100nF")
      (fields
        (field (name "BOM_Manufacturer Part") "CL05B104KO5NNNC")
        (field (name "BOM_Supplier Part") "C1525")
      )
      (libsource (lib "") (part "CL05B104KO5NNNC"))
    )
    (comp (ref "C25")
      (value "10uF")
      (fields
        (field (name "BOM_Manufacturer Part") "CL21A106KAYNNNE")
        (field (name "BOM_Supplier Part") "C15850")
      )
      (libsource (lib "") (part "CL21A106KAYNNNE"))
    )
    (comp (ref "C26")
      (value "10uF")
      (fields
        (field (name "BOM_Manufacturer Part") "CL21A106KAYNNNE")
        (field (name "BOM_Supplier Part") "C15850")
      )
      (libsource (lib "") (part "CL21A106KAYNNNE"))
    )
    (comp (ref "C27")
      (value "100nF")
      (fields
        (field (name "BOM_Manufacturer Part") "CL05B104KO5NNNC")
        (field (name "BOM_Supplier Part") "C1525")
      )
      (libsource (lib "") (part "CL05B104KO5NNNC"))
    )
    (comp (ref "C28")
      (value "100nF")
      (fields
        (field (name "BOM_Manufacturer Part") "CL05B104KO5NNNC")
        (field (name "BOM_Supplier Part") "C1525")
      )
      (libsource (lib "") (part "CL05B104KO5NNNC"))
    )
    (comp (ref "C34")
      (value "100nF")
      (fields
        (field (name "BOM_Manufacturer Part") "CL05B104KO5NNNC")
        (field (name "BOM_Supplier Part") "C1525")
      )
      (libsource (lib "") (part "CL05B104KO5NNNC"))
    )
    (comp (ref "D1")
      (value "SS34_C8678")
      (fields (field (name "BOM_Manufacturer Part") "SS34") (field (name "BOM_Supplier Part") "C8678"))
      (libsource (lib "") (part "SS34_C8678"))
    )
    (comp (ref "D2")
      (value "B5819W_C8598")
      (fields (field (name "BOM_Manufacturer Part") "B5819W") (field (name "BOM_Supplier Part") "C8598"))
      (libsource (lib "") (part "B5819W_C8598"))
    )
    (comp (ref "D4")
      (value "B5819W_C8598")
      (fields (field (name "BOM_Manufacturer Part") "B5819W") (field (name "BOM_Supplier Part") "C8598"))
      (libsource (lib "") (part "B5819W_C8598"))
    )
    (comp (ref "GND") (value "SENSOR CAP 1") (libsource (lib "") (part "TEST-POINT2_6")))
    (comp (ref "J5")
      (value "EXT SWITCH")
      (fields (field (name "BOM_Supplier Part") "C124375"))
      (libsource (lib "") (part "HDR-M-2.54_1x2_1"))
    )
    (comp (ref "J9")
      (value "EXT 5V")
      (fields (field (name "BOM_Supplier Part") "C124375"))
      (libsource (lib "") (part "HDR-M-2.54_1x2"))
    )
    (comp (ref "L1")
      (value "10uH")
      (fields
        (field (name "BOM_Manufacturer Part") "FXL0630-100-M")
        (field (name "BOM_Supplier Part") "C167223")
      )
      (libsource (lib "") (part "FXL0630-100-M"))
    )
    (comp (ref "L6")
      (value "10uH")
      (fields
        (field (name "BOM_Manufacturer Part") "FXL0630-100-M")
        (field (name "BOM_Supplier Part") "C167223")
      )
      (libsource (lib "") (part "FXL0630-100-M"))
    )
    (comp (ref "LED25")
      (value "CHARGE")
      (fields
        (field (name "BOM_Manufacturer Part") "19-217/GHC-YR1S2/3T")
        (field (name "BOM_Supplier Part") "C72043")
      )
      (libsource (lib "") (part "19-217/GHC-YR1S2/3T"))
    )
    (comp (ref "LED29")
      (value "3V3")
      (fields (field (name "BOM_Manufacturer Part") "KT-0603R") (field (name "BOM_Supplier Part") "C2286"))
      (libsource (lib "") (part "KT-0603R"))
    )
    (comp (ref "Q3")
      (value "AO3401A")
      (fields (field (name "BOM_Supplier Part") "C15127"))
      (libsource (lib "") (part "AO3401A"))
    )
    (comp (ref "Q5")
      (value "DW01")
      (fields (field (name "BOM_Supplier Part") "C181096"))
      (libsource (lib "") (part "DW01"))
    )
    (comp (ref "Q6")
      (value "FS8205A")
      (fields (field (name "BOM_Supplier Part") "C16052"))
      (libsource (lib "") (part "FS8205A"))
    )
    (comp (ref "R5")
      (value "160kΩ")
      (fields
        (field (name "BOM_Manufacturer Part") "0603WAF1603T5E")
        (field (name "BOM_Supplier Part") "C22813")
      )
      (libsource (lib "") (part "0603WAF1603T5E"))
    )
    (comp (ref "R25")
      (value "200K")
      (fields
        (field (name "BOM_Manufacturer Part") "0402WGF2003TCE")
        (field (name "BOM_Supplier Part") "C25764")
      )
      (libsource (lib "") (part "0402WGF2003TCE"))
    )
    (comp (ref "R26")
      (value "20K")
      (fields
        (field (name "BOM_Manufacturer Part") "0402WGF2002TCE")
        (field (name "BOM_Supplier Part") "C25765")
      )
      (libsource (lib "") (part "0402WGF2002TCE"))
    )
    (comp (ref "R27")
      (value "10K")
      (fields
        (field (name "BOM_Manufacturer Part") "0402WGF1002TCE")
        (field (name "BOM_Supplier Part") "C25744")
      )
      (libsource (lib "") (part "0402WGF1002TCE"))
    )
    (comp (ref "R28")
      (value "10K")
      (fields
        (field (name "BOM_Manufacturer Part") "0402WGF1002TCE")
        (field (name "BOM_Supplier Part") "C25744")
      )
      (libsource (lib "") (part "0402WGF1002TCE"))
    )
    (comp (ref "R29")
      (value "100K")
      (fields
        (field (name "BOM_Manufacturer Part") "0402WGF1003TCE")
        (field (name "BOM_Supplier Part") "C25741")
      )
      (libsource (lib "") (part "0402WGF1003TCE"))
    )
    (comp (ref "R35")
      (value "22K (1%)")
      (fields
        (field (name "BOM_Manufacturer Part") "0603WAF2202T5E")
        (field (name "BOM_Supplier Part") "C31850")
      )
      (libsource (lib "") (part "0603WAF2202T5E"))
    )
    (comp (ref "R36")
      (value "160kΩ")
      (fields
        (field (name "BOM_Manufacturer Part") "0603WAF1603T5E")
        (field (name "BOM_Supplier Part") "C22813")
      )
      (libsource (lib "") (part "0603WAF1603T5E"))
    )
    (comp (ref "R56")
      (value "22K (1%)")
      (fields
        (field (name "BOM_Manufacturer Part") "0603WAF2202T5E")
        (field (name "BOM_Supplier Part") "C31850")
      )
      (libsource (lib "") (part "0603WAF2202T5E"))
    )
    (comp (ref "R57")
      (value "1K")
      (fields
        (field (name "BOM_Manufacturer Part") "0402WGF1001TCE")
        (field (name "BOM_Supplier Part") "C11702")
      )
      (libsource (lib "") (part "0402WGF1001TCE"))
    )
    (comp (ref "R58")
      (value "100")
      (fields
        (field (name "BOM_Manufacturer Part") "0402WGF1000TCE")
        (field (name "BOM_Supplier Part") "C25076")
      )
      (libsource (lib "") (part "0402WGF1000TCE"))
    )
    (comp (ref "R60")
      (value "220K")
      (fields
        (field (name "BOM_Manufacturer Part") "0603WAF2203T5E")
        (field (name "BOM_Supplier Part") "C22961")
      )
      (libsource (lib "") (part "0603WAF2203T5E"))
    )
    (comp (ref "R61")
      (value "750K")
      (fields
        (field (name "BOM_Manufacturer Part") "0603WAF7503T5E")
        (field (name "BOM_Supplier Part") "C23240")
      )
      (libsource (lib "") (part "0603WAF7503T5E"))
    )
    (comp (ref "R63")
      (value "20K")
      (fields
        (field (name "BOM_Manufacturer Part") "0402WGF2002TCE")
        (field (name "BOM_Supplier Part") "C25765")
      )
      (libsource (lib "") (part "0402WGF2002TCE_1"))
    )
    (comp (ref "SJ3") (value "BAT PROT BYPASS") (libsource (lib "") (part "JUMPER-PAD-2-NO")))
    (comp (ref "SJ4") (value "1200 mA") (libsource (lib "") (part "JUMPER-PAD-2-NO_1")))
    (comp (ref "SW1")
      (value "TA-3524A-A1-W")
      (fields (field (name "BOM_Supplier Part") "C730329"))
      (libsource (lib "") (part "TA-3524A-A1-W"))
    )
    (comp (ref "U1")
      (value "SGM4056-6.8YPS8G/TR")
      (fields (field (name "BOM_Supplier Part") "C79687"))
      (libsource (lib "") (part "SGM4056-6.8YPS8G/TR"))
    )
    (comp (ref "U8")
      (value "HT7833-A")
      (fields (field (name "BOM_Supplier Part") "C347195"))
      (libsource (lib "") (part "HT7833-A"))
    )
    (comp (ref "U10")
      (value "MT3608L")
      (fields (field (name "BOM_Supplier Part") "C2932326"))
      (libsource (lib "") (part "MT3608L"))
    )
    (comp (ref "U11")
      (value "MT3608L")
      (fields (field (name "BOM_Supplier Part") "C2932326"))
      (libsource (lib "") (part "MT3608L"))
    )
    (comp (ref "USB2")
      (value "MICROXNJ")
      (fields (field (name "BOM_Manufacturer Part") "MicroXNJ") (field (name "BOM_Supplier Part") "C404969"))
      (libsource (lib "") (part "MICROXNJ"))
    )
    (comp (ref "VBAT") (value "SENSOR CAP 1") (libsource (lib "") (part "TEST-POINT2_4")))
    (comp (ref "VBUS") (value "SENSOR CAP 1") (libsource (lib "") (part "TEST-POINT2")))
    (comp (ref "VUSB") (value "SENSOR CAP 1") (libsource (lib "") (part "TEST-POINT2_5")))
    (comp (ref "C7")
      (value "100uF")
      (fields
        (field (name "BOM_Manufacturer Part") "TAJB107K006RNJ")
        (field (name "BOM_Supplier Part") "C16133")
      )
      (libsource (lib "") (part "TAJB107K006RNJ"))
    )
    (comp (ref "C9")
      (value "100uF")
      (fields
        (field (name "BOM_Manufacturer Part") "TAJB107K006RNJ")
        (field (name "BOM_Supplier Part") "C16133")
      )
      (libsource (lib "") (part "TAJB107K006RNJ"))
    )
    (comp (ref "C10")
      (value "100uF")
      (fields
        (field (name "BOM_Manufacturer Part") "TAJB107K006RNJ")
        (field (name "BOM_Supplier Part") "C16133")
      )
      (libsource (lib "") (part "TAJB107K006RNJ"))
    )
    (comp (ref "C12")
      (value "100uF")
      (fields
        (field (name "BOM_Manufacturer Part") "TAJB107K006RNJ")
        (field (name "BOM_Supplier Part") "C16133")
      )
      (libsource (lib "") (part "TAJB107K006RNJ"))
    )
    (comp (ref "C13")
      (value "100nF")
      (fields
        (field (name "BOM_Manufacturer Part") "CL05B104KO5NNNC")
        (field (name "BOM_Supplier Part") "C1525")
      )
      (libsource (lib "") (part "CL05B104KO5NNNC"))
    )
    (comp (ref "C22")
      (value "10uF")
      (fields
        (field (name "BOM_Manufacturer Part") "CL21A106KAYNNNE")
        (field (name "BOM_Supplier Part") "C15850")
      )
      (libsource (lib "") (part "CL21A106KAYNNNE"))
    )
    (comp (ref "C24")
      (value "10uF")
      (fields
        (field (name "BOM_Manufacturer Part") "CL21A106KAYNNNE")
        (field (name "BOM_Supplier Part") "C15850")
      )
      (libsource (lib "") (part "CL21A106KAYNNNE"))
    )
    (comp (ref "R6")
      (value "300kΩ")
      (fields
        (field (name "BOM_Manufacturer Part") "0402WGF3003TCE")
        (field (name "BOM_Supplier Part") "C25774")
      )
      (libsource (lib "") (part "0402WGF3003TCE"))
    )
    (comp (ref "R14")
      (value "680kΩ")
      (fields
        (field (name "BOM_Manufacturer Part") "0603WAF6803T5E")
        (field (name "BOM_Supplier Part") "C25822")
      )
      (libsource (lib "") (part "0603WAF6803T5E"))
    )
    (comp (ref "R22")
      (value "680kΩ")
      (fields
        (field (name "BOM_Manufacturer Part") "0603WAF6803T5E")
        (field (name "BOM_Supplier Part") "C25822")
      )
      (libsource (lib "") (part "0603WAF6803T5E"))
    )
    (comp (ref "R30")
      (value "100K (+3Db)")
      (fields
        (field (name "BOM_Manufacturer Part") "0402WGF1003TCE")
        (field (name "BOM_Supplier Part") "C25741")
      )
      (libsource (lib "") (part "0402WGF1003TCE"))
    )
    (comp (ref "R33")
      (value "100K (+15Db)")
      (fields
        (field (name "BOM_Manufacturer Part") "0402WGF1003TCE")
        (field (name "BOM_Supplier Part") "C25741")
      )
      (libsource (lib "") (part "0402WGF1003TCE"))
    )
    (comp (ref "R40")
      (value "100K (+15Db)")
      (fields
        (field (name "BOM_Manufacturer Part") "0402WGF1003TCE")
        (field (name "BOM_Supplier Part") "C25741")
      )
      (libsource (lib "") (part "0402WGF1003TCE"))
    )
    (comp (ref "R41")
      (value "100K (+3Db)")
      (fields
        (field (name "BOM_Manufacturer Part") "0402WGF1003TCE")
        (field (name "BOM_Supplier Part") "C25741")
      )
      (libsource (lib "") (part "0402WGF1003TCE"))
    )
    (comp (ref "SJ1") (value "+3Db") (libsource (lib "") (part "JUMPER-PAD-2-NO")))
    (comp (ref "SJ2") (value "+3Db") (libsource (lib "") (part "JUMPER-PAD-2-NO")))
    (comp (ref "SJ5") (value "MONO") (libsource (lib "") (part "JUMPER-PAD-2-NC_BY_TRACENO_SILK")))
    (comp (ref "SJ6") (value "+15Db") (libsource (lib "") (part "JUMPER-PAD-2-NO")))
    (comp (ref "SJ7") (value "+6Db") (libsource (lib "") (part "JUMPER-PAD-2-NO")))
    (comp (ref "SJ8") (value "+12Db") (libsource (lib "") (part "JUMPER-PAD-2-NO")))
    (comp (ref "SJ9") (value "+12Db") (libsource (lib "") (part "JUMPER-PAD-2-NO")))
    (comp (ref "SJ10") (value "+6Db") (libsource (lib "") (part "JUMPER-PAD-2-NO")))
    (comp (ref "SJ11") (value "MONO") (libsource (lib "") (part "JUMPER-PAD-2-NC_BY_TRACENO_SILK")))
    (comp (ref "SJ12") (value "+15Db") (libsource (lib "") (part "JUMPER-PAD-2-NO")))
    (comp (ref "U5")
      (value "MAX98357AETE+T")
      (fields (field (name "BOM_Supplier Part") "C910544"))
      (libsource (lib "") (part "MAX98357AETE+T"))
    )
    (comp (ref "U7")
      (value "MAX98357AETE+T")
      (fields (field (name "BOM_Supplier Part") "C910544"))
      (libsource (lib "") (part "MAX98357AETE+T"))
    )
    (comp (ref "U12")
      (value "LEFT CHANNEL")
      (fields
        (field (name "BOM_Manufacturer Part") "KF350-3.5-2P")
        (field (name "BOM_Supplier Part") "C474892")
      )
      (libsource (lib "") (part "KF350-3.5-2P"))
    )
    (comp (ref "U13")
      (value "RIGHT CHANNEL")
      (fields
        (field (name "BOM_Manufacturer Part") "KF350-3.5-2P")
        (field (name "BOM_Supplier Part") "C474892")
      )
      (libsource (lib "") (part "KF350-3.5-2P"))
    )
    (comp (ref "W")
      (value "100nF")
      (fields
        (field (name "BOM_Manufacturer Part") "CL05B104KO5NNNC")
        (field (name "BOM_Supplier Part") "C1525")
      )
      (libsource (lib "") (part "CL05B104KO5NNNC_1"))
    )
  )
  (nets
    (net (code "1") (name "3V3") (class "Default")
      (node (ref "3V3") (pin "P$1") (pinfunction "1_P$1") (pintype "unspecified"))
      (node (ref "C1") (pin "2") (pinfunction "2_2") (pintype "input"))
      (node (ref "C16") (pin "2") (pinfunction "2_2") (pintype "input"))
      (node (ref "C17") (pin "2") (pinfunction "2_2") (pintype "input"))
      (node (ref "C2") (pin "2") (pinfunction "2_2") (pintype "input"))
      (node (ref "C29") (pin "1") (pinfunction "1_1") (pintype "input"))
      (node (ref "C30") (pin "1") (pinfunction "1_1") (pintype "input"))
      (node (ref "C33") (pin "2") (pinfunction "2_2") (pintype "unspecified"))
      (node (ref "C35") (pin "1") (pinfunction "1_1") (pintype "input"))
      (node (ref "C6") (pin "2") (pinfunction "2_2") (pintype "input"))
      (node (ref "CARD1") (pin "4") (pinfunction "VDD_4") (pintype "input"))
      (node (ref "LED25") (pin "1") (pinfunction "A_1") (pintype "input"))
      (node (ref "R14") (pin "2") (pinfunction "2_2") (pintype "input"))
      (node (ref "R15") (pin "2") (pinfunction "2_2") (pintype "input"))
      (node (ref "R17") (pin "1") (pinfunction "1_1") (pintype "input"))
      (node (ref "R18") (pin "1") (pinfunction "1_1") (pintype "input"))
      (node (ref "R19") (pin "1") (pinfunction "1_1") (pintype "input"))
      (node (ref "R2") (pin "1") (pinfunction "1_1") (pintype "input"))
      (node (ref "R20") (pin "1") (pinfunction "1_1") (pintype "input"))
      (node (ref "R21") (pin "1") (pinfunction "1_1") (pintype "input"))
      (node (ref "R22") (pin "2") (pinfunction "2_2") (pintype "input"))
      (node (ref "R32") (pin "1") (pinfunction "1_1") (pintype "input"))
      (node (ref "R38") (pin "1") (pinfunction "1_1") (pintype "input"))
      (node (ref "R65") (pin "1") (pinfunction "1_1") (pintype "input"))
      (node (ref "R73") (pin "1") (pinfunction "1_1") (pintype "input"))
      (node (ref "SJ11") (pin "2") (pinfunction "2_2") (pintype "unspecified"))
      (node (ref "SJ5") (pin "2") (pinfunction "2_2") (pintype "unspecified"))
      (node (ref "U14") (pin "1") (pinfunction "1_1") (pintype "unspecified"))
      (node (ref "U15") (pin "2") (pinfunction "2_2") (pintype "unspecified"))
      (node (ref "U2") (pin "1") (pinfunction "VCC_1") (pintype "unspecified"))
      (node (ref "U3") (pin "6") (pinfunction "VDD_6") (pintype "unspecified"))
      (node (ref "U3") (pin "7") (pinfunction "REGIN_7") (pintype "unspecified"))
      (node (ref "U6") (pin "2") (pinfunction "VDD33_2") (pintype "unspecified"))
      (node (ref "U8") (pin "3") (pinfunction "VOUT_3") (pintype "unspecified"))
      (node (ref "U9") (pin "H1") (pinfunction "H+_H1") (pintype "unspecified"))
      (node (ref "U9") (pin "V1") (pinfunction "V+_V1") (pintype "unspecified"))
    )
    (net (code "2") (name "5V{slash}L") (class "Default")
      (node (ref "5V/L") (pin "P$1") (pinfunction "1_P$1") (pintype "unspecified"))
      (node (ref "C13") (pin "1") (pinfunction "1_1") (pintype "input"))
      (node (ref "C22") (pin "1") (pinfunction "1_1") (pintype "input"))
      (node (ref "C23") (pin "2") (pinfunction "2_2") (pintype "input"))
      (node (ref "C7") (pin "1") (pinfunction "1_1") (pintype "input"))
      (node (ref "C9") (pin "1") (pinfunction "1_1") (pintype "input"))
      (node (ref "D4") (pin "1") (pinfunction "-_1") (pintype "unspecified"))
      (node (ref "R36") (pin "2") (pinfunction "2_2") (pintype "input"))
      (node (ref "SJ1") (pin "2") (pinfunction "2_2") (pintype "unspecified"))
      (node (ref "SJ7") (pin "2") (pinfunction "2_2") (pintype "unspecified"))
      (node (ref "U5") (pin "7") (pinfunction "VDD_7") (pintype "unspecified"))
      (node (ref "U5") (pin "8") (pinfunction "VDD_8") (pintype "unspecified"))
    )
    (net (code "3") (name "5V{slash}R") (class "Default")
      (node (ref "5V/R") (pin "P$1") (pinfunction "1_P$1") (pintype "unspecified"))
      (node (ref "C10") (pin "1") (pinfunction "1_1") (pintype "input"))
      (node (ref "C12") (pin "1") (pinfunction "1_1") (pintype "input"))
      (node (ref "C24") (pin "1") (pinfunction "1_1") (pintype "input"))
      (node (ref "C26") (pin "2") (pinfunction "2_2") (pintype "input"))
      (node (ref "C27") (pin "2") (pinfunction "2_2") (pintype "input"))
      (node (ref "D2") (pin "1") (pinfunction "-_1") (pintype "unspecified"))
      (node (ref "R5") (pin "2") (pinfunction "2_2") (pintype "input"))
      (node (ref "SJ10") (pin "2") (pinfunction "2_2") (pintype "unspecified"))
      (node (ref "SJ2") (pin "2") (pinfunction "2_2") (pintype "unspecified"))
      (node (ref "U7") (pin "7") (pinfunction "VDD_7") (pintype "unspecified"))
      (node (ref "U7") (pin "8") (pinfunction "VDD_8") (pintype "unspecified"))
      (node (ref "W") (pin "1") (pinfunction "1_1") (pintype "input"))
    )
    (net (code "4") (name "BAT_GND") (class "Default")
      (node (ref "BATT1") (pin "3") (pinfunction "3_3") (pintype "unspecified"))
      (node (ref "BATT1") (pin "4") (pinfunction "4_4") (pintype "unspecified"))
      (node (ref "BT1") (pin "2") (pinfunction "-_2") (pintype "passive"))
      (node (ref "BT2") (pin "2") (pinfunction "-_2") (pintype "passive"))
      (node (ref "BTGND") (pin "P$1") (pinfunction "1_P$1") (pintype "unspecified"))
      (node (ref "C34") (pin "1") (pinfunction "1_1") (pintype "input"))
      (node (ref "Q5") (pin "6") (pinfunction "GND_6") (pintype "unspecified"))
      (node (ref "Q6") (pin "6") (pinfunction "S2_6") (pintype "unspecified"))
      (node (ref "Q6") (pin "7") (pinfunction "S2_7") (pintype "unspecified"))
      (node (ref "SJ3") (pin "2") (pinfunction "2_2") (pintype "unspecified"))
    )
    (net (code "5") (name "DTR") (class "Default")
      (node (ref "Q2") (pin "2") (pinfunction "E_2") (pintype "unspecified"))
      (node (ref "R3") (pin "1") (pinfunction "1_1") (pintype "input"))
      (node (ref "U3") (pin "28") (pinfunction "DTR_28") (pintype "unspecified"))
    )
    (net (code "6") (name "GND") (class "Default")
      (node (ref "BATT1") (pin "1") (pinfunction "1_1") (pintype "unspecified"))
      (node (ref "C1") (pin "1") (pinfunction "1_1") (pintype "input"))
      (node (ref "C10") (pin "2") (pinfunction "2_2") (pintype "input"))
      (node (ref "C11") (pin "1") (pinfunction "1_1") (pintype "input"))
      (node (ref "C12") (pin "2") (pinfunction "2_2") (pintype "input"))
      (node (ref "C13") (pin "2") (pinfunction "2_2") (pintype "input"))
      (node (ref "C14") (pin "1") (pinfunction "1_1") (pintype "input"))
      (node (ref "C15") (pin "1") (pinfunction "1_1") (pintype "input"))
      (node (ref "C16") (pin "1") (pinfunction "1_1") (pintype "input"))
      (node (ref "C17") (pin "1") (pinfunction "1_1") (pintype "input"))
      (node (ref "C18") (pin "1") (pinfunction "1_1") (pintype "input"))
      (node (ref "C19") (pin "1") (pinfunction "1_1") (pintype "input"))
      (node (ref "C2") (pin "1") (pinfunction "1_1") (pintype "input"))
      (node (ref "C20") (pin "1") (pinfunction "1_1") (pintype "input"))
      (node (ref "C21") (pin "1") (pinfunction "1_1") (pintype "input"))
      (node (ref "C22") (pin "2") (pinfunction "2_2") (pintype "input"))
      (node (ref "C23") (pin "1") (pinfunction "1_1") (pintype "input"))
      (node (ref "C24") (pin "2") (pinfunction "2_2") (pintype "input"))
      (node (ref "C25") (pin "1") (pinfunction "1_1") (pintype "input"))
      (node (ref "C26") (pin "1") (pinfunction "1_1") (pintype "input"))
      (node (ref "C27") (pin "1") (pinfunction "1_1") (pintype "input"))
      (node (ref "C28") (pin "1") (pinfunction "1_1") (pintype "input"))
      (node (ref "C29") (pin "2") (pinfunction "2_2") (pintype "input"))
      (node (ref "C3") (pin "2") (pinfunction "2_2") (pintype "input"))
      (node (ref "C30") (pin "2") (pinfunction "2_2") (pintype "input"))
      (node (ref "C31") (pin "1") (pinfunction "1_1") (pintype "unspecified"))
      (node (ref "C32") (pin "2") (pinfunction "2_2") (pintype "input"))
      (node (ref "C33") (pin "1") (pinfunction "1_1") (pintype "unspecified"))
      (node (ref "C35") (pin "2") (pinfunction "2_2") (pintype "input"))
      (node (ref "C4") (pin "1") (pinfunction "1_1") (pintype "input"))
      (node (ref "C5") (pin "1") (pinfunction "1_1") (pintype "input"))
      (node (ref "C6") (pin "1") (pinfunction "1_1") (pintype "input"))
      (node (ref "C7") (pin "2") (pinfunction "2_2") (pintype "input"))
      (node (ref "C8") (pin "2") (pinfunction "2_2") (pintype "input"))
      (node (ref "C9") (pin "2") (pinfunction "2_2") (pintype "input"))
      (node (ref "CARD1") (pin "10") (pinfunction "GND_10") (pintype "input"))
      (node (ref "CARD1") (pin "11") (pinfunction "GND_11") (pintype "input"))
      (node (ref "CARD1") (pin "12") (pinfunction "GND_12") (pintype "input"))
      (node (ref "CARD1") (pin "13") (pinfunction "GND_13") (pintype "input"))
      (node (ref "CARD1") (pin "6") (pinfunction "VSS_6") (pintype "input"))
      (node (ref "D3") (pin "2") (pinfunction "GND_2") (pintype "unspecified"))
      (node (ref "EN1") (pin "1") (pinfunction "SWA_1") (pintype "unspecified"))
      (node (ref "EN1") (pin "3") (pinfunction "COM_3") (pintype "unspecified"))
      (node (ref "GND") (pin "P$1") (pinfunction "1_P$1") (pintype "unspecified"))
      (node (ref "H2") (pin "1") (pinfunction "1_1") (pintype "unspecified"))
      (node (ref "H3") (pin "1") (pinfunction "1_1") (pintype "unspecified"))
      (node (ref "J4") (pin "1") (pinfunction "1_1") (pintype "input"))
      (node (ref "J9") (pin "1") (pinfunction "1_1") (pintype "unspecified"))
      (node (ref "LED2") (pin "3") (pinfunction "GND_3") (pintype "unspecified"))
      (node (ref "LED23") (pin "1") (pinfunction "GND_1") (pintype "unspecified"))
      (node (ref "LED23") (pin "2") (pinfunction "GND_2") (pintype "unspecified"))
      (node (ref "Q6") (pin "2") (pinfunction "S1_2") (pintype "unspecified"))
      (node (ref "Q6") (pin "3") (pinfunction "S1_3") (pintype "unspecified"))
      (node (ref "R25") (pin "2") (pinfunction "2_2") (pintype "input"))
      (node (ref "R26") (pin "2") (pinfunction "2_2") (pintype "input"))
      (node (ref "R29") (pin "1") (pinfunction "1_1") (pintype "input"))
      (node (ref "R35") (pin "1") (pinfunction "1_1") (pintype "input"))
      (node (ref "R56") (pin "1") (pinfunction "1_1") (pintype "input"))
      (node (ref "R57") (pin "2") (pinfunction "2_2") (pintype "input"))
      (node (ref "R60") (pin "1") (pinfunction "1_1") (pintype "input"))
      (node (ref "SJ12") (pin "1") (pinfunction "1_1") (pintype "unspecified"))
      (node (ref "SJ3") (pin "1") (pinfunction "1_1") (pintype "unspecified"))
      (node (ref "SJ4") (pin "1") (pinfunction "1_1") (pintype "unspecified"))
      (node (ref "SJ6") (pin "1") (pinfunction "1_1") (pintype "unspecified"))
      (node (ref "SJ8") (pin "1") (pinfunction "1_1") (pintype "unspecified"))
      (node (ref "SJ9") (pin "1") (pinfunction "1_1") (pintype "unspecified"))
      (node (ref "SW1") (pin "4") (pinfunction "4_4") (pintype "unspecified"))
      (node (ref "SW1") (pin "5") (pinfunction "5_5") (pintype "unspecified"))
      (node (ref "SW1") (pin "6") (pinfunction "6_6") (pintype "unspecified"))
      (node (ref "SW1") (pin "7") (pinfunction "7_7") (pintype "unspecified"))
      (node (ref "SW3") (pin "1") (pinfunction "A_1") (pintype "unspecified"))
      (node (ref "SW3") (pin "2") (pinfunction "B_2") (pintype "unspecified"))
      (node (ref "SW5") (pin "1") (pinfunction "A_1") (pintype "unspecified"))
      (node (ref "SW5") (pin "2") (pinfunction "B_2") (pintype "unspecified"))
      (node (ref "U1") (pin "5") (pinfunction "GND_5") (pintype "unspecified"))
      (node (ref "U1") (pin "9") (pinfunction "EP_9") (pintype "unspecified"))
      (node (ref "U10") (pin "2") (pinfunction "GND_2") (pintype "unspecified"))
      (node (ref "U11") (pin "2") (pinfunction "GND_2") (pintype "unspecified"))
      (node (ref "U14") (pin "2") (pinfunction "2_2") (pintype "unspecified"))
      (node (ref "U15") (pin "1") (pinfunction "1_1") (pintype "unspecified"))
      (node (ref "U2") (pin "2") (pinfunction "GND_2") (pintype "unspecified"))
      (node (ref "U3") (pin "29") (pinfunction "EP_29") (pintype "unspecified"))
      (node (ref "U3") (pin "3") (pinfunction "GND_3") (pintype "unspecified"))
      (node (ref "U5") (pin "11") (pinfunction "GND_11") (pintype "unspecified"))
      (node (ref "U5") (pin "15") (pinfunction "GND_15") (pintype "unspecified"))
      (node (ref "U5") (pin "17") (pinfunction "EP_17") (pintype "unspecified"))
      (node (ref "U5") (pin "3") (pinfunction "GND_3") (pintype "unspecified"))
      (node (ref "U6") (pin "1") (pinfunction "GND_1") (pintype "unspecified"))
      (node (ref "U6") (pin "15") (pinfunction "GND_15") (pintype "unspecified"))
      (node (ref "U6") (pin "38") (pinfunction "GND_38") (pintype "unspecified"))
      (node (ref "U6") (pin "39") (pinfunction "GND_39") (pintype "unspecified"))
      (node (ref "U7") (pin "11") (pinfunction "GND_11") (pintype "unspecified"))
      (node (ref "U7") (pin "15") (pinfunction "GND_15") (pintype "unspecified"))
      (node (ref "U7") (pin "17") (pinfunction "EP_17") (pintype "unspecified"))
      (node (ref "U7") (pin "3") (pinfunction "GND_3") (pintype "unspecified"))
      (node (ref "U8") (pin "1") (pinfunction "GND_1") (pintype "unspecified"))
      (node (ref "U9") (pin "B2A") (pinfunction "SEL-_B2A") (pintype "unspecified"))
      (node (ref "U9") (pin "H3") (pinfunction "H-_H3") (pintype "unspecified"))
      (node (ref "U9") (pin "V3") (pinfunction "V-_V3") (pintype "unspecified"))
      (node (ref "USB2") (pin "5") (pinfunction "GND_5") (pintype "unspecified"))
      (node (ref "USB2") (pin "6") (pinfunction "SH1_6") (pintype "unspecified"))
      (node (ref "USB2") (pin "7") (pinfunction "SH2_7") (pintype "unspecified"))
      (node (ref "USB2") (pin "8") (pinfunction "SH3_8") (pintype "unspecified"))
      (node (ref "USB2") (pin "9") (pinfunction "SH4_9") (pintype "unspecified"))
      (node (ref "W") (pin "2") (pinfunction "2_2") (pintype "input"))
    )
    (net (code "7") (name "GPIO0") (class "Default")
      (node (ref "BTN1") (pin "P$1") (pinfunction "1_P$1") (pintype "unspecified"))
      (node (ref "H5") (pin "3") (pinfunction "3_3") (pintype "unspecified"))
      (node (ref "LED23") (pin "3") (pinfunction "OUT_3") (pintype "unspecified"))
      (node (ref "Q2") (pin "3") (pinfunction "C_3") (pintype "unspecified"))
      (node (ref "R21") (pin "2") (pinfunction "2_2") (pintype "input"))
      (node (ref "R72") (pin "2") (pinfunction "2_2") (pintype "input"))
      (node (ref "SW5") (pin "3") (pinfunction "C_3") (pintype "unspecified"))
      (node (ref "SW5") (pin "4") (pinfunction "D_4") (pintype "unspecified"))
      (node (ref "U6") (pin "25") (pinfunction "IO0_25") (pintype "unspecified"))
    )
    (net (code "8") (name "GPIO01") (class "Default")
      (node (ref "R12") (pin "1") (pinfunction "1_1") (pintype "input"))
      (node (ref "U6") (pin "35") (pinfunction "TXD0_35") (pintype "unspecified"))
    )
    (net (code "9") (name "GPIO02") (class "Default")
      (node (ref "BTN2") (pin "P$1") (pinfunction "1_P$1") (pintype "unspecified"))
      (node (ref "H5") (pin "2") (pinfunction "2_2") (pintype "unspecified"))
      (node (ref "U14") (pin "11") (pinfunction "11_11") (pintype "unspecified"))
      (node (ref "U2") (pin "11") (pinfunction "T_CS_11") (pintype "unspecified"))
      (node (ref "U6") (pin "24") (pinfunction "IO2_24") (pintype "unspecified"))
    )
    (net (code "10") (name "GPIO03") (class "Default")
      (node (ref "R13") (pin "1") (pinfunction "1_1") (pintype "input"))
      (node (ref "U6") (pin "34") (pinfunction "RXD0_34") (pintype "unspecified"))
    )
    (net (code "11") (name "GPIO04") (class "Default")
      (node (ref "BTN0") (pin "P$1") (pinfunction "1_P$1") (pintype "unspecified"))
      (node (ref "H5") (pin "4") (pinfunction "4_4") (pintype "unspecified"))
      (node (ref "U14") (pin "5") (pinfunction "5_5") (pintype "unspecified"))
      (node (ref "U2") (pin "5") (pinfunction "D/C_5") (pintype "unspecified"))
      (node (ref "U6") (pin "26") (pinfunction "IO4_26") (pintype "unspecified"))
    )
    (net (code "12") (name "GPIO05") (class "Default")
      (node (ref "H5") (pin "7") (pinfunction "7_7") (pintype "unspecified"))
      (node (ref "U14") (pin "3") (pinfunction "3_3") (pintype "unspecified"))
      (node (ref "U2") (pin "3") (pinfunction "CS_3") (pintype "unspecified"))
      (node (ref "U6") (pin "29") (pinfunction "IO5_29") (pintype "unspecified"))
    )
    (net (code "13") (name "GPIO12") (class "Default")
      (node (ref "BTN5") (pin "P$1") (pinfunction "1_P$1") (pintype "unspecified"))
      (node (ref "H1") (pin "11") (pinfunction "11_11") (pintype "unspecified"))
      (node (ref "H2") (pin "6") (pinfunction "6_6") (pintype "unspecified"))
      (node (ref "J4") (pin "6") (pinfunction "6_6") (pintype "input"))
      (node (ref "U6") (pin "14") (pinfunction "IO12_14") (pintype "unspecified"))
    )
    (net (code "14") (name "GPIO13") (class "Default")
      (node (ref "BTN4") (pin "P$1") (pinfunction "1_P$1") (pintype "unspecified"))
      (node (ref "H1") (pin "12") (pinfunction "12_12") (pintype "unspecified"))
      (node (ref "H2") (pin "5") (pinfunction "5_5") (pintype "unspecified"))
      (node (ref "J4") (pin "5") (pinfunction "5_5") (pintype "input"))
      (node (ref "U6") (pin "16") (pinfunction "IO13_16") (pintype "unspecified"))
    )
    (net (code "15") (name "GPIO14") (class "Default")
      (node (ref "BTN6") (pin "P$1") (pinfunction "1_P$1") (pintype "unspecified"))
      (node (ref "H1") (pin "10") (pinfunction "10_10") (pintype "unspecified"))
      (node (ref "H2") (pin "4") (pinfunction "4_4") (pintype "unspecified"))
      (node (ref "J4") (pin "4") (pinfunction "4_4") (pintype "input"))
      (node (ref "U6") (pin "13") (pinfunction "IO14_13") (pintype "unspecified"))
    )
    (net (code "16") (name "GPIO15") (class "Default")
      (node (ref "BTN3") (pin "P$1") (pinfunction "1_P$1") (pintype "unspecified"))
      (node (ref "H2") (pin "3") (pinfunction "3_3") (pintype "unspecified"))
      (node (ref "H5") (pin "1") (pinfunction "1_1") (pintype "unspecified"))
      (node (ref "J4") (pin "3") (pinfunction "3_3") (pintype "input"))
      (node (ref "U6") (pin "23") (pinfunction "IO15_23") (pintype "unspecified"))
    )
    (net (code "17") (name "GPIO18") (class "Default")
      (node (ref "CARD1") (pin "5") (pinfunction "CLK(SCLK)_5") (pintype "input"))
      (node (ref "H5") (pin "8") (pinfunction "8_8") (pintype "unspecified"))
      (node (ref "U14") (pin "10") (pinfunction "10_10") (pintype "unspecified"))
      (node (ref "U14") (pin "7") (pinfunction "7_7") (pintype "unspecified"))
      (node (ref "U2") (pin "10") (pinfunction "T_CLK_10") (pintype "unspecified"))
      (node (ref "U2") (pin "18") (pinfunction "SD_CLK_18") (pintype "unspecified"))
      (node (ref "U2") (pin "7") (pinfunction "SCK_7") (pintype "unspecified"))
      (node (ref "U4") (pin "1") (pinfunction "1_1") (pintype "unspecified"))
      (node (ref "U6") (pin "30") (pinfunction "IO18_30") (pintype "unspecified"))
    )
    (net (code "18") (name "GPIO19") (class "Default")
      (node (ref "CARD1") (pin "7") (pinfunction "DAT0(D0)_7") (pintype "bidirectional"))
      (node (ref "H5") (pin "9") (pinfunction "9_9") (pintype "unspecified"))
      (node (ref "R17") (pin "2") (pinfunction "2_2") (pintype "input"))
      (node (ref "U14") (pin "13") (pinfunction "13_13") (pintype "unspecified"))
      (node (ref "U14") (pin "9") (pinfunction "9_9") (pintype "unspecified"))
      (node (ref "U2") (pin "13") (pinfunction "T_DO_13") (pintype "unspecified"))
      (node (ref "U2") (pin "17") (pinfunction "SD_MISO_17") (pintype "unspecified"))
      (node (ref "U2") (pin "9") (pinfunction "MISO_9") (pintype "unspecified"))
      (node (ref "U4") (pin "2") (pinfunction "2_2") (pintype "unspecified"))
      (node (ref "U6") (pin "31") (pinfunction "IO19_31") (pintype "unspecified"))
    )
    (net (code "19") (name "GPIO21") (class "Default")
      (node (ref "H5") (pin "10") (pinfunction "10_10") (pintype "unspecified"))
      (node (ref "R28") (pin "2") (pinfunction "2_2") (pintype "input"))
      (node (ref "U1") (pin "3") (pinfunction "CHG#_3") (pintype "unspecified"))
      (node (ref "U6") (pin "33") (pinfunction "IO21_33") (pintype "unspecified"))
    )
    (net (code "20") (name "GPIO22") (class "Default")
      (node (ref "H5") (pin "11") (pinfunction "11_11") (pintype "unspecified"))
      (node (ref "U5") (pin "1") (pinfunction "DIN_1") (pintype "unspecified"))
      (node (ref "U6") (pin "36") (pinfunction "IO22_36") (pintype "unspecified"))
      (node (ref "U7") (pin "1") (pinfunction "DIN_1") (pintype "unspecified"))
    )
    (net (code "21") (name "GPIO23") (class "Default")
      (node (ref "CARD1") (pin "3") (pinfunction "CMD(DI)_3") (pintype "input"))
      (node (ref "H5") (pin "12") (pinfunction "12_12") (pintype "unspecified"))
      (node (ref "R20") (pin "2") (pinfunction "2_2") (pintype "input"))
      (node (ref "U14") (pin "12") (pinfunction "12_12") (pintype "unspecified"))
      (node (ref "U14") (pin "6") (pinfunction "6_6") (pintype "unspecified"))
      (node (ref "U2") (pin "12") (pinfunction "T_DI_12") (pintype "unspecified"))
      (node (ref "U2") (pin "16") (pinfunction "SD_MOSI_16") (pintype "unspecified"))
      (node (ref "U2") (pin "6") (pinfunction "MOSI_6") (pintype "unspecified"))
      (node (ref "U4") (pin "3") (pinfunction "3_3") (pintype "unspecified"))
      (node (ref "U6") (pin "37") (pinfunction "IO23_37") (pintype "unspecified"))
    )
    (net (code "22") (name "GPIO25") (class "Default")
      (node (ref "H1") (pin "7") (pinfunction "7_7") (pintype "unspecified"))
      (node (ref "U5") (pin "14") (pinfunction "LRCLK_14") (pintype "unspecified"))
      (node (ref "U6") (pin "10") (pinfunction "IO25_10") (pintype "unspecified"))
      (node (ref "U7") (pin "14") (pinfunction "LRCLK_14") (pintype "unspecified"))
    )
    (net (code "23") (name "GPIO26") (class "Default")
      (node (ref "H1") (pin "8") (pinfunction "8_8") (pintype "unspecified"))
      (node (ref "U5") (pin "16") (pinfunction "BCLK_16") (pintype "unspecified"))
      (node (ref "U6") (pin "11") (pinfunction "IO26_11") (pintype "unspecified"))
      (node (ref "U7") (pin "16") (pinfunction "BCLK_16") (pintype "unspecified"))
    )
    (net (code "24") (name "GPIO27") (class "Default")
      (node (ref "BTN7") (pin "P$1") (pinfunction "1_P$1") (pintype "unspecified"))
      (node (ref "CARD1") (pin "2") (pinfunction "CDDAT3(CS)_2") (pintype "bidirectional"))
      (node (ref "H1") (pin "9") (pinfunction "9_9") (pintype "unspecified"))
      (node (ref "R73") (pin "2") (pinfunction "2_2") (pintype "input"))
      (node (ref "U2") (pin "15") (pinfunction "SD_CS_15") (pintype "unspecified"))
      (node (ref "U4") (pin "4") (pinfunction "4_4") (pintype "unspecified"))
      (node (ref "U6") (pin "12") (pinfunction "IO27_12") (pintype "unspecified"))
    )
    (net (code "25") (name "GPIO32") (class "Default")
      (node (ref "BTN9") (pin "P$1") (pinfunction "1_P$1") (pintype "unspecified"))
      (node (ref "H1") (pin "5") (pinfunction "5_5") (pintype "unspecified"))
      (node (ref "R4") (pin "2") (pinfunction "2_2") (pintype "input"))
      (node (ref "U14") (pin "4") (pinfunction "4_4") (pintype "unspecified"))
      (node (ref "U2") (pin "4") (pinfunction "RESET_4") (pintype "unspecified"))
      (node (ref "U6") (pin "8") (pinfunction "IO32_8") (pintype "unspecified"))
    )
    (net (code "26") (name "GPIO33") (class "Default")
      (node (ref "BTN8") (pin "P$1") (pinfunction "1_P$1") (pintype "unspecified"))
      (node (ref "H1") (pin "6") (pinfunction "6_6") (pintype "unspecified"))
      (node (ref "R39") (pin "2") (pinfunction "2_2") (pintype "input"))
      (node (ref "U6") (pin "9") (pinfunction "IO33_9") (pintype "unspecified"))
    )
    (net (code "27") (name "GPIO34") (class "Default")
      (node (ref "H1") (pin "3") (pinfunction "3_3") (pintype "unspecified"))
      (node (ref "R60") (pin "2") (pinfunction "2_2") (pintype "input"))
      (node (ref "R61") (pin "1") (pinfunction "1_1") (pintype "input"))
      (node (ref "U6") (pin "6") (pinfunction "IO34_6") (pintype "unspecified"))
    )
    (net (code "28") (name "GPIO35") (class "Default")
      (node (ref "EN1") (pin "5") (pinfunction "B_5") (pintype "unspecified"))
      (node (ref "H1") (pin "4") (pinfunction "4_4") (pintype "unspecified"))
      (node (ref "R32") (pin "2") (pinfunction "2_2") (pintype "input"))
      (node (ref "U15") (pin "4") (pinfunction "4_4") (pintype "unspecified"))
      (node (ref "U6") (pin "7") (pinfunction "IO35_7") (pintype "unspecified"))
      (node (ref "U9") (pin "H2") (pinfunction "H_H2") (pintype "unspecified"))
    )
    (net (code "29") (name "GPIO36") (class "Default")
      (node (ref "EN1") (pin "4") (pinfunction "A_4") (pintype "unspecified"))
      (node (ref "H1") (pin "1") (pinfunction "1_1") (pintype "unspecified"))
      (node (ref "R38") (pin "2") (pinfunction "2_2") (pintype "input"))
      (node (ref "U15") (pin "3") (pinfunction "3_3") (pintype "unspecified"))
      (node (ref "U6") (pin "4") (pinfunction "SENSOR_VP_4") (pintype "unspecified"))
      (node (ref "U9") (pin "V2") (pinfunction "V_V2") (pintype "unspecified"))
    )
    (net (code "30") (name "GPIO39") (class "Default")
      (node (ref "C15") (pin "2") (pinfunction "2_2") (pintype "input"))
      (node (ref "EN1") (pin "2") (pinfunction "2_2") (pintype "unspecified"))
      (node (ref "H1") (pin "2") (pinfunction "2_2") (pintype "unspecified"))
      (node (ref "R65") (pin "2") (pinfunction "2_2") (pintype "input"))
      (node (ref "U15") (pin "5") (pinfunction "5_5") (pintype "unspecified"))
      (node (ref "U6") (pin "5") (pinfunction "SENSOR_VN_5") (pintype "unspecified"))
      (node (ref "U9") (pin "B1A") (pinfunction "SEL+_B1A") (pintype "unspecified"))
    )
    (net (code "31") (name "MCU_RST") (class "Default")
      (node (ref "C3") (pin "1") (pinfunction "1_1") (pintype "input"))
      (node (ref "H2") (pin "2") (pinfunction "2_2") (pintype "unspecified"))
      (node (ref "J4") (pin "2") (pinfunction "2_2") (pintype "input"))
      (node (ref "Q1") (pin "3") (pinfunction "C_3") (pintype "unspecified"))
      (node (ref "R2") (pin "2") (pinfunction "2_2") (pintype "input"))
      (node (ref "SW3") (pin "3") (pinfunction "C_3") (pintype "unspecified"))
      (node (ref "SW3") (pin "4") (pinfunction "D_4") (pintype "unspecified"))
      (node (ref "U6") (pin "3") (pinfunction "EN_3") (pintype "unspecified"))
    )
    (net (code "32") (name "MCU_RX") (class "Default")
      (node (ref "R13") (pin "2") (pinfunction "2_2") (pintype "input"))
      (node (ref "U3") (pin "26") (pinfunction "TXD_26") (pintype "unspecified"))
    )
    (net (code "33") (name "MCU_TX") (class "Default")
      (node (ref "R12") (pin "2") (pinfunction "2_2") (pintype "input"))
      (node (ref "U3") (pin "25") (pinfunction "RXD_25") (pintype "unspecified"))
    )
    (net (code "34") (name "Net-(CARD1-DAT1(RSV))") (class "Default")
      (node (ref "CARD1") (pin "8") (pinfunction "DAT1(RSV)_8") (pintype "bidirectional"))
      (node (ref "R18") (pin "2") (pinfunction "2_2") (pintype "input"))
    )
    (net (code "35") (name "Net-(CARD1-DAT2(RSV))") (class "Default")
      (node (ref "CARD1") (pin "1") (pinfunction "DAT2(RSV)_1") (pintype "bidirectional"))
      (node (ref "R19") (pin "2") (pinfunction "2_2") (pintype "input"))
    )
    (net (code "36") (name "Net-(D1-K)") (class "Default")
      (node (ref "D1") (pin "1") (pinfunction "K_1") (pintype "unspecified"))
      (node (ref "J5") (pin "2") (pinfunction "2_2") (pintype "unspecified"))
      (node (ref "Q3") (pin "2") (pinfunction "S_2") (pintype "unspecified"))
      (node (ref "SW1") (pin "1") (pinfunction "1_1") (pintype "unspecified"))
    )
    (net (code "37") (name "Net-(D2-+)") (class "Default")
      (node (ref "D2") (pin "2") (pinfunction "+_2") (pintype "unspecified"))
      (node (ref "L6") (pin "2") (pinfunction "2_2") (pintype "unspecified"))
      (node (ref "U10") (pin "1") (pinfunction "SW_1") (pintype "unspecified"))
    )
    (net (code "38") (name "Net-(D4-+)") (class "Default")
      (node (ref "D4") (pin "2") (pinfunction "+_2") (pintype "unspecified"))
      (node (ref "L1") (pin "2") (pinfunction "2_2") (pintype "unspecified"))
      (node (ref "U11") (pin "1") (pinfunction "SW_1") (pintype "unspecified"))
    )
    (net (code "39") (name "Net-(LED2-DIN)") (class "Default")
      (node (ref "LED2") (pin "4") (pinfunction "DIN_4") (pintype "unspecified"))
      (node (ref "R39") (pin "1") (pinfunction "1_1") (pintype "input"))
    )
    (net (code "40") (name "Net-(LED2-DO)") (class "Default")
      (node (ref "H3") (pin "2") (pinfunction "2_2") (pintype "unspecified"))
      (node (ref "LED2") (pin "2") (pinfunction "DO_2") (pintype "unspecified"))
    )
    (net (code "41") (name "Net-(LED23-VCC)") (class "Default")
      (node (ref "C31") (pin "2") (pinfunction "2_2") (pintype "unspecified"))
      (node (ref "C32") (pin "1") (pinfunction "1_1") (pintype "input"))
      (node (ref "LED23") (pin "4") (pinfunction "VCC_4") (pintype "unspecified"))
      (node (ref "R15") (pin "1") (pinfunction "1_1") (pintype "input"))
      (node (ref "R72") (pin "1") (pinfunction "1_1") (pintype "input"))
    )
    (net (code "42") (name "Net-(LED25-C)") (class "Default")
      (node (ref "LED25") (pin "2") (pinfunction "C_2") (pintype "input"))
      (node (ref "R28") (pin "1") (pinfunction "1_1") (pintype "input"))
    )
    (net (code "43") (name "Net-(LED29-K)") (class "Default")
      (node (ref "LED29") (pin "2") (pinfunction "K_2") (pintype "unspecified"))
      (node (ref "R27") (pin "1") (pinfunction "1_1") (pintype "input"))
    )
    (net (code "44") (name "Net-(Q1-B)") (class "Default")
      (node (ref "Q1") (pin "1") (pinfunction "B_1") (pintype "unspecified"))
      (node (ref "R3") (pin "2") (pinfunction "2_2") (pintype "input"))
    )
    (net (code "45") (name "Net-(Q2-B)") (class "Default")
      (node (ref "Q2") (pin "1") (pinfunction "B_1") (pintype "unspecified"))
      (node (ref "R9") (pin "2") (pinfunction "2_2") (pintype "input"))
    )
    (net (code "46") (name "Net-(Q5-CS)") (class "Default")
      (node (ref "Q5") (pin "2") (pinfunction "CS_2") (pintype "unspecified"))
      (node (ref "R57") (pin "1") (pinfunction "1_1") (pintype "input"))
    )
    (net (code "47") (name "Net-(Q5-OC)") (class "Default")
      (node (ref "Q5") (pin "3") (pinfunction "OC_3") (pintype "unspecified"))
      (node (ref "Q6") (pin "4") (pinfunction "G1_4") (pintype "unspecified"))
    )
    (net (code "48") (name "Net-(Q5-OD)") (class "Default")
      (node (ref "Q5") (pin "1") (pinfunction "OD_1") (pintype "unspecified"))
      (node (ref "Q6") (pin "5") (pinfunction "G2_5") (pintype "unspecified"))
    )
    (net (code "49") (name "Net-(Q5-VCC)") (class "Default")
      (node (ref "C34") (pin "2") (pinfunction "2_2") (pintype "input"))
      (node (ref "Q5") (pin "5") (pinfunction "VCC_5") (pintype "unspecified"))
      (node (ref "R58") (pin "2") (pinfunction "2_2") (pintype "input"))
    )
    (net (code "50") (name "Net-(Q6-D12-Pad1)") (class "Default")
      (node (ref "Q6") (pin "1") (pinfunction "D12_1") (pintype "unspecified"))
      (node (ref "Q6") (pin "8") (pinfunction "D12_8") (pintype "unspecified"))
    )
    (net (code "51") (name "Net-(R6-Pad2)") (class "Default")
      (node (ref "R6") (pin "2") (pinfunction "2_2") (pintype "input"))
      (node (ref "SJ11") (pin "1") (pinfunction "1_1") (pintype "unspecified"))
    )
    (net (code "52") (name "Net-(R30-Pad2)") (class "Default")
      (node (ref "R30") (pin "2") (pinfunction "2_2") (pintype "input"))
      (node (ref "SJ2") (pin "1") (pinfunction "1_1") (pintype "unspecified"))
    )
    (net (code "53") (name "Net-(R33-Pad1)") (class "Default")
      (node (ref "R33") (pin "1") (pinfunction "1_1") (pintype "input"))
      (node (ref "SJ12") (pin "2") (pinfunction "2_2") (pintype "unspecified"))
    )
    (net (code "54") (name "Net-(R40-Pad1)") (class "Default")
      (node (ref "R40") (pin "1") (pinfunction "1_1") (pintype "input"))
      (node (ref "SJ6") (pin "2") (pinfunction "2_2") (pintype "unspecified"))
    )
    (net (code "55") (name "Net-(R41-Pad2)") (class "Default")
      (node (ref "R41") (pin "2") (pinfunction "2_2") (pintype "input"))
      (node (ref "SJ1") (pin "1") (pinfunction "1_1") (pintype "unspecified"))
    )
    (net (code "56") (name "Net-(R63-Pad2)") (class "Default")
      (node (ref "R63") (pin "2") (pinfunction "2_2") (pintype "input"))
      (node (ref "SJ4") (pin "2") (pinfunction "2_2") (pintype "unspecified"))
    )
    (net (code "57") (name "Net-(U1-IMIN)") (class "Default")
      (node (ref "R25") (pin "1") (pinfunction "1_1") (pintype "input"))
      (node (ref "U1") (pin "6") (pinfunction "IMIN_6") (pintype "unspecified"))
    )
    (net (code "58") (name "Net-(U1-IREF)") (class "Default")
      (node (ref "R26") (pin "1") (pinfunction "1_1") (pintype "input"))
      (node (ref "R63") (pin "1") (pinfunction "1_1") (pintype "input"))
      (node (ref "U1") (pin "7") (pinfunction "IREF_7") (pintype "unspecified"))
    )
    (net (code "59") (name "Net-(U1-PPR#)") (class "Default")
      (node (ref "R27") (pin "2") (pinfunction "2_2") (pintype "input"))
      (node (ref "U1") (pin "2") (pinfunction "PPR#_2") (pintype "unspecified"))
    )
    (net (code "60") (name "Net-(U3-D+)") (class "Default")
      (node (ref "D3") (pin "6") (pinfunction "IO1_6") (pintype "unspecified"))
      (node (ref "U3") (pin "4") (pinfunction "D+_4") (pintype "unspecified"))
    )
    (net (code "61") (name "Net-(U3-D-)") (class "Default")
      (node (ref "D3") (pin "4") (pinfunction "IO2_4") (pintype "unspecified"))
      (node (ref "U3") (pin "5") (pinfunction "D-_5") (pintype "unspecified"))
    )
    (net (code "62") (name "Net-(U5-GAIN_SLOT)") (class "Default")
      (node (ref "R40") (pin "2") (pinfunction "2_2") (pintype "input"))
      (node (ref "R41") (pin "1") (pinfunction "1_1") (pintype "input"))
      (node (ref "SJ7") (pin "1") (pinfunction "1_1") (pintype "unspecified"))
      (node (ref "SJ8") (pin "2") (pinfunction "2_2") (pintype "unspecified"))
      (node (ref "U5") (pin "2") (pinfunction "GAIN_SLOT_2") (pintype "unspecified"))
    )
    (net (code "63") (name "Net-(U5-OUTN)") (class "Default")
      (node (ref "U12") (pin "2") (pinfunction "2_2") (pintype "unspecified"))
      (node (ref "U5") (pin "10") (pinfunction "OUTN_10") (pintype "unspecified"))
    )
    (net (code "64") (name "Net-(U5-OUTP)") (class "Default")
      (node (ref "U12") (pin "1") (pinfunction "1_1") (pintype "unspecified"))
      (node (ref "U5") (pin "9") (pinfunction "OUTP_9") (pintype "unspecified"))
    )
    (net (code "65") (name "Net-(U5-SD_MODE#)") (class "Default")
      (node (ref "R14") (pin "1") (pinfunction "1_1") (pintype "input"))
      (node (ref "SJ5") (pin "1") (pinfunction "1_1") (pintype "unspecified"))
      (node (ref "U5") (pin "4") (pinfunction "SD_MODE#_4") (pintype "unspecified"))
    )
    (net (code "66") (name "Net-(U7-GAIN_SLOT)") (class "Default")
      (node (ref "R30") (pin "1") (pinfunction "1_1") (pintype "input"))
      (node (ref "R33") (pin "2") (pinfunction "2_2") (pintype "input"))
      (node (ref "SJ10") (pin "1") (pinfunction "1_1") (pintype "unspecified"))
      (node (ref "SJ9") (pin "2") (pinfunction "2_2") (pintype "unspecified"))
      (node (ref "U7") (pin "2") (pinfunction "GAIN_SLOT_2") (pintype "unspecified"))
    )
    (net (code "67") (name "Net-(U7-OUTN)") (class "Default")
      (node (ref "U13") (pin "2") (pinfunction "2_2") (pintype "unspecified"))
      (node (ref "U7") (pin "10") (pinfunction "OUTN_10") (pintype "unspecified"))
    )
    (net (code "68") (name "Net-(U7-OUTP)") (class "Default")
      (node (ref "U13") (pin "1") (pinfunction "1_1") (pintype "unspecified"))
      (node (ref "U7") (pin "9") (pinfunction "OUTP_9") (pintype "unspecified"))
    )
    (net (code "69") (name "Net-(U7-SD_MODE#)") (class "Default")
      (node (ref "R22") (pin "1") (pinfunction "1_1") (pintype "input"))
      (node (ref "R6") (pin "1") (pinfunction "1_1") (pintype "input"))
      (node (ref "U7") (pin "4") (pinfunction "SD_MODE#_4") (pintype "unspecified"))
    )
    (net (code "70") (name "Net-(U10-FB)") (class "Default")
      (node (ref "R5") (pin "1") (pinfunction "1_1") (pintype "input"))
      (node (ref "R56") (pin "2") (pinfunction "2_2") (pintype "input"))
      (node (ref "U10") (pin "3") (pinfunction "FB_3") (pintype "unspecified"))
    )
    (net (code "71") (name "Net-(U11-FB)") (class "Default")
      (node (ref "R35") (pin "2") (pinfunction "2_2") (pintype "input"))
      (node (ref "R36") (pin "1") (pinfunction "1_1") (pintype "input"))
      (node (ref "U11") (pin "3") (pinfunction "FB_3") (pintype "unspecified"))
    )
    (net (code "72") (name "RTS") (class "Default")
      (node (ref "Q1") (pin "2") (pinfunction "E_2") (pintype "unspecified"))
      (node (ref "R9") (pin "1") (pinfunction "1_1") (pintype "input"))
      (node (ref "U3") (pin "24") (pinfunction "RTS_24") (pintype "unspecified"))
    )
    (net (code "73") (name "TCH_IRQ") (class "Default")
      (node (ref "U14") (pin "14") (pinfunction "14_14") (pintype "unspecified"))
      (node (ref "U2") (pin "14") (pinfunction "T_IRQ_14") (pintype "unspecified"))
    )
    (net (code "74") (name "TFT_LED") (class "Default")
      (node (ref "R4") (pin "1") (pinfunction "1_1") (pintype "input"))
      (node (ref "U14") (pin "8") (pinfunction "8_8") (pintype "unspecified"))
      (node (ref "U2") (pin "8") (pinfunction "LED_8") (pintype "unspecified"))
    )
    (net (code "75") (name "USBM") (class "Default")
      (node (ref "D3") (pin "3") (pinfunction "IO2_3") (pintype "unspecified"))
      (node (ref "USB2") (pin "2") (pinfunction "D-_2") (pintype "unspecified"))
    )
    (net (code "76") (name "USBP") (class "Default")
      (node (ref "D3") (pin "1") (pinfunction "IO1_1") (pintype "unspecified"))
      (node (ref "USB2") (pin "3") (pinfunction "D+_3") (pintype "unspecified"))
    )
    (net (code "77") (name "VBAT") (class "Default")
      (node (ref "BATT1") (pin "2") (pinfunction "2_2") (pintype "unspecified"))
      (node (ref "BT1") (pin "1") (pinfunction "+_1") (pintype "passive"))
      (node (ref "BT2") (pin "1") (pinfunction "+_1") (pintype "passive"))
      (node (ref "C20") (pin "2") (pinfunction "2_2") (pintype "input"))
      (node (ref "LED29") (pin "1") (pinfunction "A_1") (pintype "unspecified"))
      (node (ref "Q3") (pin "3") (pinfunction "D_3") (pintype "unspecified"))
      (node (ref "R58") (pin "1") (pinfunction "1_1") (pintype "input"))
      (node (ref "R61") (pin "2") (pinfunction "2_2") (pintype "input"))
      (node (ref "U1") (pin "8") (pinfunction "BAT_8") (pintype "unspecified"))
      (node (ref "VBAT") (pin "P$1") (pinfunction "1_P$1") (pintype "unspecified"))
    )
    (net (code "78") (name "VBUS") (class "Default")
      (node (ref "C11") (pin "2") (pinfunction "2_2") (pintype "input"))
      (node (ref "C14") (pin "2") (pinfunction "2_2") (pintype "input"))
      (node (ref "C18") (pin "2") (pinfunction "2_2") (pintype "input"))
      (node (ref "C19") (pin "2") (pinfunction "2_2") (pintype "input"))
      (node (ref "C25") (pin "2") (pinfunction "2_2") (pintype "input"))
      (node (ref "C28") (pin "2") (pinfunction "2_2") (pintype "input"))
      (node (ref "C8") (pin "1") (pinfunction "1_1") (pintype "input"))
      (node (ref "H3") (pin "3") (pinfunction "3_3") (pintype "unspecified"))
      (node (ref "J5") (pin "1") (pinfunction "1_1") (pintype "unspecified"))
      (node (ref "L1") (pin "1") (pinfunction "1_1") (pintype "unspecified"))
      (node (ref "L6") (pin "1") (pinfunction "1_1") (pintype "unspecified"))
      (node (ref "LED2") (pin "1") (pinfunction "VDD_1") (pintype "unspecified"))
      (node (ref "SW1") (pin "2") (pinfunction "2_2") (pintype "unspecified"))
      (node (ref "U10") (pin "4") (pinfunction "EN_4") (pintype "unspecified"))
      (node (ref "U10") (pin "5") (pinfunction "VIN_5") (pintype "unspecified"))
      (node (ref "U11") (pin "4") (pinfunction "EN_4") (pintype "unspecified"))
      (node (ref "U11") (pin "5") (pinfunction "VIN_5") (pintype "unspecified"))
      (node (ref "U8") (pin "2") (pinfunction "VIN_2") (pintype "unspecified"))
      (node (ref "VBUS") (pin "P$1") (pinfunction "1_P$1") (pintype "unspecified"))
    )
    (net (code "79") (name "VUSB") (class "Default")
      (node (ref "C21") (pin "2") (pinfunction "2_2") (pintype "input"))
      (node (ref "C4") (pin "2") (pinfunction "2_2") (pintype "input"))
      (node (ref "C5") (pin "2") (pinfunction "2_2") (pintype "input"))
      (node (ref "D1") (pin "2") (pinfunction "A_2") (pintype "unspecified"))
      (node (ref "D3") (pin "5") (pinfunction "VBUS_5") (pintype "unspecified"))
      (node (ref "J9") (pin "2") (pinfunction "2_2") (pintype "unspecified"))
      (node (ref "Q3") (pin "1") (pinfunction "G_1") (pintype "unspecified"))
      (node (ref "R29") (pin "2") (pinfunction "2_2") (pintype "input"))
      (node (ref "U1") (pin "1") (pinfunction "VIN_1") (pintype "unspecified"))
      (node (ref "U3") (pin "8") (pinfunction "VBUS_8") (pintype "unspecified"))
      (node (ref "USB2") (pin "1") (pinfunction "VBUS_1") (pintype "unspecified"))
      (node (ref "VUSB") (pin "P$1") (pinfunction "1_P$1") (pintype "unspecified"))
    )
    (net (code "80") (name "unconnected-(CARD1-CD-Pad9)") (class "Default")
      (node (ref "CARD1") (pin "9") (pinfunction "CD_9") (pintype "input+no_connect"))
    )
    (net (code "81") (name "unconnected-(H5-Pad5)") (class "Default")
      (node (ref "H5") (pin "5") (pinfunction "5_5") (pintype "unspecified+no_connect"))
    )
    (net (code "82") (name "unconnected-(H5-Pad6)") (class "Default")
      (node (ref "H5") (pin "6") (pinfunction "6_6") (pintype "unspecified+no_connect"))
    )
    (net (code "83") (name "unconnected-(Q5-TD-Pad4)") (class "Default")
      (node (ref "Q5") (pin "4") (pinfunction "TD_4") (pintype "unspecified+no_connect"))
    )
    (net (code "84") (name "unconnected-(SW1-Pad3)") (class "Default")
      (node (ref "SW1") (pin "3") (pinfunction "3_3") (pintype "unspecified+no_connect"))
    )
    (net (code "85") (name "unconnected-(U1-EN#-Pad4)") (class "Default")
      (node (ref "U1") (pin "4") (pinfunction "EN#_4") (pintype "unspecified+no_connect"))
    )
    (net (code "86") (name "unconnected-(U3-CTS-Pad23)") (class "Default")
      (node (ref "U3") (pin "23") (pinfunction "CTS_23") (pintype "unspecified+no_connect"))
    )
    (net (code "87") (name "unconnected-(U3-DCD-Pad1)") (class "Default")
      (node (ref "U3") (pin "1") (pinfunction "DCD_1") (pintype "unspecified+no_connect"))
    )
    (net (code "88") (name "unconnected-(U3-DSR-Pad27)") (class "Default")
      (node (ref "U3") (pin "27") (pinfunction "DSR_27") (pintype "unspecified+no_connect"))
    )
    (net (code "89") (name "unconnected-(U3-NC-Pad10)") (class "Default")
      (node (ref "U3") (pin "10") (pinfunction "NC_10") (pintype "unspecified+no_connect"))
    )
    (net (code "90") (name "unconnected-(U3-NC-Pad13)") (class "Default")
      (node (ref "U3") (pin "13") (pinfunction "NC_13") (pintype "unspecified+no_connect"))
    )
    (net (code "91") (name "unconnected-(U3-NC-Pad14)") (class "Default")
      (node (ref "U3") (pin "14") (pinfunction "NC_14") (pintype "unspecified+no_connect"))
    )
    (net (code "92") (name "unconnected-(U3-NC-Pad15)") (class "Default")
      (node (ref "U3") (pin "15") (pinfunction "NC_15") (pintype "unspecified+no_connect"))
    )
    (net (code "93") (name "unconnected-(U3-NC-Pad16)") (class "Default")
      (node (ref "U3") (pin "16") (pinfunction "NC_16") (pintype "unspecified+no_connect"))
    )
    (net (code "94") (name "unconnected-(U3-NC-Pad17)") (class "Default")
      (node (ref "U3") (pin "17") (pinfunction "NC_17") (pintype "unspecified+no_connect"))
    )
    (net (code "95") (name "unconnected-(U3-NC-Pad18)") (class "Default")
      (node (ref "U3") (pin "18") (pinfunction "NC_18") (pintype "unspecified+no_connect"))
    )
    (net (code "96") (name "unconnected-(U3-NC-Pad19)") (class "Default")
      (node (ref "U3") (pin "19") (pinfunction "NC_19") (pintype "unspecified+no_connect"))
    )
    (net (code "97") (name "unconnected-(U3-NC-Pad20)") (class "Default")
      (node (ref "U3") (pin "20") (pinfunction "NC_20") (pintype "unspecified+no_connect"))
    )
    (net (code "98") (name "unconnected-(U3-NC-Pad21)") (class "Default")
      (node (ref "U3") (pin "21") (pinfunction "NC_21") (pintype "unspecified+no_connect"))
    )
    (net (code "99") (name "unconnected-(U3-NC-Pad22)") (class "Default")
      (node (ref "U3") (pin "22") (pinfunction "NC_22") (pintype "unspecified+no_connect"))
    )
    (net (code "100") (name "unconnected-(U3-RI-Pad2)") (class "Default")
      (node (ref "U3") (pin "2") (pinfunction "RI_2") (pintype "unspecified+no_connect"))
    )
    (net (code "101") (name "unconnected-(U3-RST#-Pad9)") (class "Default")
      (node (ref "U3") (pin "9") (pinfunction "RST#_9") (pintype "unspecified+no_connect"))
    )
    (net (code "102") (name "unconnected-(U3-SUSPEND#-Pad11)") (class "Default")
      (node (ref "U3") (pin "11") (pinfunction "SUSPEND#_11") (pintype "unspecified+no_connect"))
    )
    (net (code "103") (name "unconnected-(U3-SUSPEND-Pad12)") (class "Default")
      (node (ref "U3") (pin "12") (pinfunction "SUSPEND_12") (pintype "unspecified+no_connect"))
    )
    (net (code "104") (name "unconnected-(U5-N.C.-Pad5)") (class "Default")
      (node (ref "U5") (pin "5") (pinfunction "N.C._5") (pintype "unspecified+no_connect"))
    )
    (net (code "105") (name "unconnected-(U5-N.C.-Pad6)") (class "Default")
      (node (ref "U5") (pin "6") (pinfunction "N.C._6") (pintype "unspecified+no_connect"))
    )
    (net (code "106") (name "unconnected-(U5-N.C.-Pad12)") (class "Default")
      (node (ref "U5") (pin "12") (pinfunction "N.C._12") (pintype "unspecified+no_connect"))
    )
    (net (code "107") (name "unconnected-(U5-N.C.-Pad13)") (class "Default")
      (node (ref "U5") (pin "13") (pinfunction "N.C._13") (pintype "unspecified+no_connect"))
    )
    (net (code "108") (name "unconnected-(U6-CLK-Pad20)") (class "Default")
      (node (ref "U6") (pin "20") (pinfunction "CLK_20") (pintype "unspecified+no_connect"))
    )
    (net (code "109") (name "unconnected-(U6-CMD-Pad19)") (class "Default")
      (node (ref "U6") (pin "19") (pinfunction "CMD_19") (pintype "unspecified+no_connect"))
    )
    (net (code "110") (name "unconnected-(U6-NC-Pad27)") (class "Default")
      (node (ref "U6") (pin "27") (pinfunction "NC_27") (pintype "unspecified+no_connect"))
    )
    (net (code "111") (name "unconnected-(U6-NC-Pad28)") (class "Default")
      (node (ref "U6") (pin "28") (pinfunction "NC_28") (pintype "unspecified+no_connect"))
    )
    (net (code "112") (name "unconnected-(U6-NC-Pad32)") (class "Default")
      (node (ref "U6") (pin "32") (pinfunction "NC_32") (pintype "unspecified+no_connect"))
    )
    (net (code "113") (name "unconnected-(U6-SD0-Pad21)") (class "Default")
      (node (ref "U6") (pin "21") (pinfunction "SD0_21") (pintype "unspecified+no_connect"))
    )
    (net (code "114") (name "unconnected-(U6-SD1-Pad22)") (class "Default")
      (node (ref "U6") (pin "22") (pinfunction "SD1_22") (pintype "unspecified+no_connect"))
    )
    (net (code "115") (name "unconnected-(U6-SD2-Pad17)") (class "Default")
      (node (ref "U6") (pin "17") (pinfunction "SD2_17") (pintype "unspecified+no_connect"))
    )
    (net (code "116") (name "unconnected-(U6-SD3-Pad18)") (class "Default")
      (node (ref "U6") (pin "18") (pinfunction "SD3_18") (pintype "unspecified+no_connect"))
    )
    (net (code "117") (name "unconnected-(U7-N.C.-Pad5)") (class "Default")
      (node (ref "U7") (pin "5") (pinfunction "N.C._5") (pintype "unspecified+no_connect"))
    )
    (net (code "118") (name "unconnected-(U7-N.C.-Pad6)") (class "Default")
      (node (ref "U7") (pin "6") (pinfunction "N.C._6") (pintype "unspecified+no_connect"))
    )
    (net (code "119") (name "unconnected-(U7-N.C.-Pad12)") (class "Default")
      (node (ref "U7") (pin "12") (pinfunction "N.C._12") (pintype "unspecified+no_connect"))
    )
    (net (code "120") (name "unconnected-(U7-N.C.-Pad13)") (class "Default")
      (node (ref "U7") (pin "13") (pinfunction "N.C._13") (pintype "unspecified+no_connect"))
    )
    (net (code "121") (name "unconnected-(U10-OC-Pad6)") (class "Default")
      (node (ref "U10") (pin "6") (pinfunction "OC_6") (pintype "unspecified+no_connect"))
    )
    (net (code "122") (name "unconnected-(U11-OC-Pad6)") (class "Default")
      (node (ref "U11") (pin "6") (pinfunction "OC_6") (pintype "unspecified+no_connect"))
    )
    (net (code "123") (name "unconnected-(USB2-ID-Pad4)") (class "Default")
      (node (ref "USB2") (pin "4") (pinfunction "ID_4") (pintype "unspecified+no_connect"))
    )
  )
)
